# paris_wheel.net
KiCad netlist of a schematic drawn in EAGLE
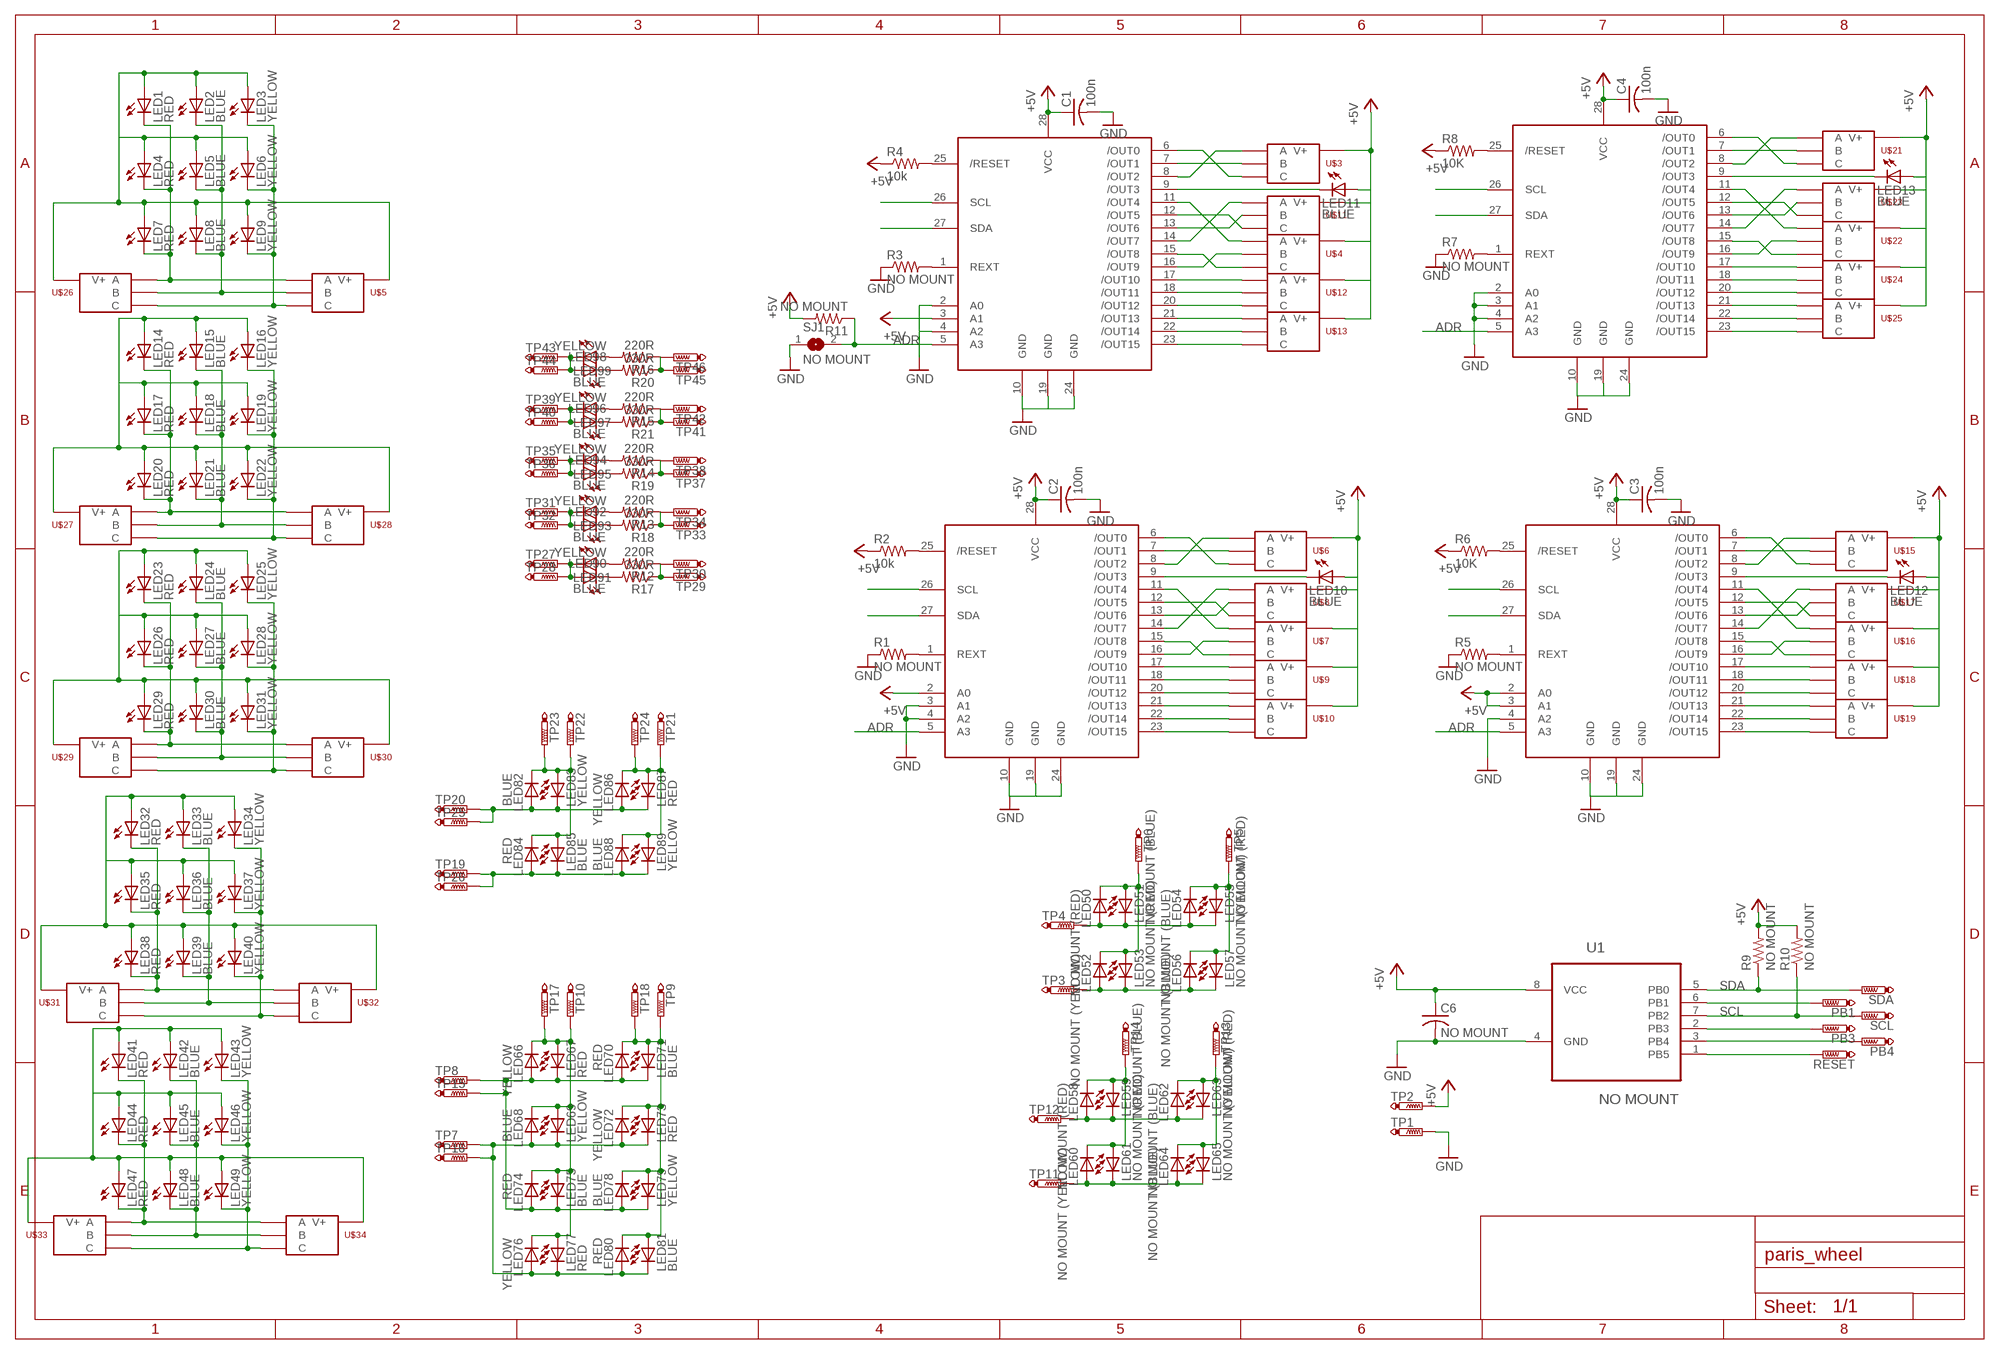
[diagram p0: schematic, sheet 1]

(export (version "E")
  (design (tool "Eeschema 10.0.6"))
  (components
    (comp (ref "C1")
      (value "100n")
      (footprint "eagle-import:C0603")
      (libsource (lib "eagle-import") (part "C-USC0603"))
    )
    (comp (ref "C2")
      (value "100n")
      (footprint "eagle-import:C0603")
      (libsource (lib "eagle-import") (part "C-USC0603"))
    )
    (comp (ref "C3")
      (value "100n")
      (footprint "eagle-import:C0603")
      (libsource (lib "eagle-import") (part "C-USC0603"))
    )
    (comp (ref "C4")
      (value "100n")
      (footprint "eagle-import:C0603")
      (libsource (lib "eagle-import") (part "C-USC0603"))
    )
    (comp (ref "C6")
      (value "NO MOUNT")
      (footprint "eagle-import:C0603")
      (libsource (lib "eagle-import") (part "C-USC0603"))
    )
    (comp (ref "LED1")
      (value "RED")
      (footprint "eagle-import:CHIP-LED0603")
      (libsource (lib "eagle-import") (part "LEDCHIP-LED0603"))
    )
    (comp (ref "LED2")
      (value "BLUE")
      (footprint "eagle-import:CHIP-LED0603")
      (libsource (lib "eagle-import") (part "LEDCHIP-LED0603"))
    )
    (comp (ref "LED3")
      (value "YELLOW")
      (footprint "eagle-import:CHIP-LED0603")
      (libsource (lib "eagle-import") (part "LEDCHIP-LED0603"))
    )
    (comp (ref "LED4")
      (value "RED")
      (footprint "eagle-import:CHIP-LED0603")
      (libsource (lib "eagle-import") (part "LEDCHIP-LED0603"))
    )
    (comp (ref "LED5")
      (value "BLUE")
      (footprint "eagle-import:CHIP-LED0603")
      (libsource (lib "eagle-import") (part "LEDCHIP-LED0603"))
    )
    (comp (ref "LED6")
      (value "YELLOW")
      (footprint "eagle-import:CHIP-LED0603")
      (libsource (lib "eagle-import") (part "LEDCHIP-LED0603"))
    )
    (comp (ref "LED7")
      (value "RED")
      (footprint "eagle-import:CHIP-LED0603")
      (libsource (lib "eagle-import") (part "LEDCHIP-LED0603"))
    )
    (comp (ref "LED8")
      (value "BLUE")
      (footprint "eagle-import:CHIP-LED0603")
      (libsource (lib "eagle-import") (part "LEDCHIP-LED0603"))
    )
    (comp (ref "LED9")
      (value "YELLOW")
      (footprint "eagle-import:CHIP-LED0603")
      (libsource (lib "eagle-import") (part "LEDCHIP-LED0603"))
    )
    (comp (ref "LED10")
      (value "BLUE")
      (footprint "eagle-import:CHIP-LED0603")
      (libsource (lib "eagle-import") (part "LEDCHIP-LED0603"))
    )
    (comp (ref "LED11")
      (value "BLUE")
      (footprint "eagle-import:CHIP-LED0603")
      (libsource (lib "eagle-import") (part "LEDCHIP-LED0603"))
    )
    (comp (ref "LED12")
      (value "BLUE")
      (footprint "eagle-import:CHIP-LED0603")
      (libsource (lib "eagle-import") (part "LEDCHIP-LED0603"))
    )
    (comp (ref "LED13")
      (value "BLUE")
      (footprint "eagle-import:CHIP-LED0603")
      (libsource (lib "eagle-import") (part "LEDCHIP-LED0603"))
    )
    (comp (ref "LED14")
      (value "RED")
      (footprint "eagle-import:CHIP-LED0603")
      (libsource (lib "eagle-import") (part "LEDCHIP-LED0603"))
    )
    (comp (ref "LED15")
      (value "BLUE")
      (footprint "eagle-import:CHIP-LED0603")
      (libsource (lib "eagle-import") (part "LEDCHIP-LED0603"))
    )
    (comp (ref "LED16")
      (value "YELLOW")
      (footprint "eagle-import:CHIP-LED0603")
      (libsource (lib "eagle-import") (part "LEDCHIP-LED0603"))
    )
    (comp (ref "LED17")
      (value "RED")
      (footprint "eagle-import:CHIP-LED0603")
      (libsource (lib "eagle-import") (part "LEDCHIP-LED0603"))
    )
    (comp (ref "LED18")
      (value "BLUE")
      (footprint "eagle-import:CHIP-LED0603")
      (libsource (lib "eagle-import") (part "LEDCHIP-LED0603"))
    )
    (comp (ref "LED19")
      (value "YELLOW")
      (footprint "eagle-import:CHIP-LED0603")
      (libsource (lib "eagle-import") (part "LEDCHIP-LED0603"))
    )
    (comp (ref "LED20")
      (value "RED")
      (footprint "eagle-import:CHIP-LED0603")
      (libsource (lib "eagle-import") (part "LEDCHIP-LED0603"))
    )
    (comp (ref "LED21")
      (value "BLUE")
      (footprint "eagle-import:CHIP-LED0603")
      (libsource (lib "eagle-import") (part "LEDCHIP-LED0603"))
    )
    (comp (ref "LED22")
      (value "YELLOW")
      (footprint "eagle-import:CHIP-LED0603")
      (libsource (lib "eagle-import") (part "LEDCHIP-LED0603"))
    )
    (comp (ref "LED23")
      (value "RED")
      (footprint "eagle-import:CHIP-LED0603")
      (libsource (lib "eagle-import") (part "LEDCHIP-LED0603"))
    )
    (comp (ref "LED24")
      (value "BLUE")
      (footprint "eagle-import:CHIP-LED0603")
      (libsource (lib "eagle-import") (part "LEDCHIP-LED0603"))
    )
    (comp (ref "LED25")
      (value "YELLOW")
      (footprint "eagle-import:CHIP-LED0603")
      (libsource (lib "eagle-import") (part "LEDCHIP-LED0603"))
    )
    (comp (ref "LED26")
      (value "RED")
      (footprint "eagle-import:CHIP-LED0603")
      (libsource (lib "eagle-import") (part "LEDCHIP-LED0603"))
    )
    (comp (ref "LED27")
      (value "BLUE")
      (footprint "eagle-import:CHIP-LED0603")
      (libsource (lib "eagle-import") (part "LEDCHIP-LED0603"))
    )
    (comp (ref "LED28")
      (value "YELLOW")
      (footprint "eagle-import:CHIP-LED0603")
      (libsource (lib "eagle-import") (part "LEDCHIP-LED0603"))
    )
    (comp (ref "LED29")
      (value "RED")
      (footprint "eagle-import:CHIP-LED0603")
      (libsource (lib "eagle-import") (part "LEDCHIP-LED0603"))
    )
    (comp (ref "LED30")
      (value "BLUE")
      (footprint "eagle-import:CHIP-LED0603")
      (libsource (lib "eagle-import") (part "LEDCHIP-LED0603"))
    )
    (comp (ref "LED31")
      (value "YELLOW")
      (footprint "eagle-import:CHIP-LED0603")
      (libsource (lib "eagle-import") (part "LEDCHIP-LED0603"))
    )
    (comp (ref "LED32")
      (value "RED")
      (footprint "eagle-import:CHIP-LED0603")
      (libsource (lib "eagle-import") (part "LEDCHIP-LED0603"))
    )
    (comp (ref "LED33")
      (value "BLUE")
      (footprint "eagle-import:CHIP-LED0603")
      (libsource (lib "eagle-import") (part "LEDCHIP-LED0603"))
    )
    (comp (ref "LED34")
      (value "YELLOW")
      (footprint "eagle-import:CHIP-LED0603")
      (libsource (lib "eagle-import") (part "LEDCHIP-LED0603"))
    )
    (comp (ref "LED35")
      (value "RED")
      (footprint "eagle-import:CHIP-LED0603")
      (libsource (lib "eagle-import") (part "LEDCHIP-LED0603"))
    )
    (comp (ref "LED36")
      (value "BLUE")
      (footprint "eagle-import:CHIP-LED0603")
      (libsource (lib "eagle-import") (part "LEDCHIP-LED0603"))
    )
    (comp (ref "LED37")
      (value "YELLOW")
      (footprint "eagle-import:CHIP-LED0603")
      (libsource (lib "eagle-import") (part "LEDCHIP-LED0603"))
    )
    (comp (ref "LED38")
      (value "RED")
      (footprint "eagle-import:CHIP-LED0603")
      (libsource (lib "eagle-import") (part "LEDCHIP-LED0603"))
    )
    (comp (ref "LED39")
      (value "BLUE")
      (footprint "eagle-import:CHIP-LED0603")
      (libsource (lib "eagle-import") (part "LEDCHIP-LED0603"))
    )
    (comp (ref "LED40")
      (value "YELLOW")
      (footprint "eagle-import:CHIP-LED0603")
      (libsource (lib "eagle-import") (part "LEDCHIP-LED0603"))
    )
    (comp (ref "LED41")
      (value "RED")
      (footprint "eagle-import:CHIP-LED0603")
      (libsource (lib "eagle-import") (part "LEDCHIP-LED0603"))
    )
    (comp (ref "LED42")
      (value "BLUE")
      (footprint "eagle-import:CHIP-LED0603")
      (libsource (lib "eagle-import") (part "LEDCHIP-LED0603"))
    )
    (comp (ref "LED43")
      (value "YELLOW")
      (footprint "eagle-import:CHIP-LED0603")
      (libsource (lib "eagle-import") (part "LEDCHIP-LED0603"))
    )
    (comp (ref "LED44")
      (value "RED")
      (footprint "eagle-import:CHIP-LED0603")
      (libsource (lib "eagle-import") (part "LEDCHIP-LED0603"))
    )
    (comp (ref "LED45")
      (value "BLUE")
      (footprint "eagle-import:CHIP-LED0603")
      (libsource (lib "eagle-import") (part "LEDCHIP-LED0603"))
    )
    (comp (ref "LED46")
      (value "YELLOW")
      (footprint "eagle-import:CHIP-LED0603")
      (libsource (lib "eagle-import") (part "LEDCHIP-LED0603"))
    )
    (comp (ref "LED47")
      (value "RED")
      (footprint "eagle-import:CHIP-LED0603")
      (libsource (lib "eagle-import") (part "LEDCHIP-LED0603"))
    )
    (comp (ref "LED48")
      (value "BLUE")
      (footprint "eagle-import:CHIP-LED0603")
      (libsource (lib "eagle-import") (part "LEDCHIP-LED0603"))
    )
    (comp (ref "LED49")
      (value "YELLOW")
      (footprint "eagle-import:CHIP-LED0603")
      (libsource (lib "eagle-import") (part "LEDCHIP-LED0603"))
    )
    (comp (ref "LED50")
      (value "NO MOUNT (RED)")
      (footprint "eagle-import:CHIP-LED0603")
      (libsource (lib "eagle-import") (part "LEDCHIP-LED0603"))
    )
    (comp (ref "LED51")
      (value "NO MOUNT (BLUE)")
      (footprint "eagle-import:CHIP-LED0603")
      (libsource (lib "eagle-import") (part "LEDCHIP-LED0603"))
    )
    (comp (ref "LED52")
      (value "NO MOUNT (YELLOW)")
      (footprint "eagle-import:CHIP-LED0603")
      (libsource (lib "eagle-import") (part "LEDCHIP-LED0603"))
    )
    (comp (ref "LED53")
      (value "NO MOUNT (RED)")
      (footprint "eagle-import:CHIP-LED0603")
      (libsource (lib "eagle-import") (part "LEDCHIP-LED0603"))
    )
    (comp (ref "LED54")
      (value "NO MOUNT (BLUE)")
      (footprint "eagle-import:CHIP-LED0603")
      (libsource (lib "eagle-import") (part "LEDCHIP-LED0603"))
    )
    (comp (ref "LED55")
      (value "NO MOUNT (RED)")
      (footprint "eagle-import:CHIP-LED0603")
      (libsource (lib "eagle-import") (part "LEDCHIP-LED0603"))
    )
    (comp (ref "LED56")
      (value "NO MOUNT (BLUE)")
      (footprint "eagle-import:CHIP-LED0603")
      (libsource (lib "eagle-import") (part "LEDCHIP-LED0603"))
    )
    (comp (ref "LED57")
      (value "NO MOUNT (YELLOW)")
      (footprint "eagle-import:CHIP-LED0603")
      (libsource (lib "eagle-import") (part "LEDCHIP-LED0603"))
    )
    (comp (ref "LED58")
      (value "NO MOUNT (RED)")
      (footprint "eagle-import:CHIP-LED0603")
      (libsource (lib "eagle-import") (part "LEDCHIP-LED0603"))
    )
    (comp (ref "LED59")
      (value "NO MOUNT (BLUE)")
      (footprint "eagle-import:CHIP-LED0603")
      (libsource (lib "eagle-import") (part "LEDCHIP-LED0603"))
    )
    (comp (ref "LED60")
      (value "NO MOUNT (YELLOW)")
      (footprint "eagle-import:CHIP-LED0603")
      (libsource (lib "eagle-import") (part "LEDCHIP-LED0603"))
    )
    (comp (ref "LED61")
      (value "NO MOUNT (RED)")
      (footprint "eagle-import:CHIP-LED0603")
      (libsource (lib "eagle-import") (part "LEDCHIP-LED0603"))
    )
    (comp (ref "LED62")
      (value "NO MOUNT (BLUE)")
      (footprint "eagle-import:CHIP-LED0603")
      (libsource (lib "eagle-import") (part "LEDCHIP-LED0603"))
    )
    (comp (ref "LED63")
      (value "NO MOUNT (RED)")
      (footprint "eagle-import:CHIP-LED0603")
      (libsource (lib "eagle-import") (part "LEDCHIP-LED0603"))
    )
    (comp (ref "LED64")
      (value "NO MOUNT (BLUE)")
      (footprint "eagle-import:CHIP-LED0603")
      (libsource (lib "eagle-import") (part "LEDCHIP-LED0603"))
    )
    (comp (ref "LED65")
      (value "NO MOUNT (YELLOW)")
      (footprint "eagle-import:CHIP-LED0603")
      (libsource (lib "eagle-import") (part "LEDCHIP-LED0603"))
    )
    (comp (ref "LED66")
      (value "YELLOW")
      (footprint "eagle-import:CHIP-LED0603")
      (libsource (lib "eagle-import") (part "LEDCHIP-LED0603"))
    )
    (comp (ref "LED67")
      (value "RED")
      (footprint "eagle-import:CHIP-LED0603")
      (libsource (lib "eagle-import") (part "LEDCHIP-LED0603"))
    )
    (comp (ref "LED68")
      (value "BLUE")
      (footprint "eagle-import:CHIP-LED0603")
      (libsource (lib "eagle-import") (part "LEDCHIP-LED0603"))
    )
    (comp (ref "LED69")
      (value "YELLOW")
      (footprint "eagle-import:CHIP-LED0603")
      (libsource (lib "eagle-import") (part "LEDCHIP-LED0603"))
    )
    (comp (ref "LED70")
      (value "RED")
      (footprint "eagle-import:CHIP-LED0603")
      (libsource (lib "eagle-import") (part "LEDCHIP-LED0603"))
    )
    (comp (ref "LED71")
      (value "BLUE")
      (footprint "eagle-import:CHIP-LED0603")
      (libsource (lib "eagle-import") (part "LEDCHIP-LED0603"))
    )
    (comp (ref "LED72")
      (value "YELLOW")
      (footprint "eagle-import:CHIP-LED0603")
      (libsource (lib "eagle-import") (part "LEDCHIP-LED0603"))
    )
    (comp (ref "LED73")
      (value "RED")
      (footprint "eagle-import:CHIP-LED0603")
      (libsource (lib "eagle-import") (part "LEDCHIP-LED0603"))
    )
    (comp (ref "LED74")
      (value "RED")
      (footprint "eagle-import:CHIP-LED0603")
      (libsource (lib "eagle-import") (part "LEDCHIP-LED0603"))
    )
    (comp (ref "LED75")
      (value "BLUE")
      (footprint "eagle-import:CHIP-LED0603")
      (libsource (lib "eagle-import") (part "LEDCHIP-LED0603"))
    )
    (comp (ref "LED76")
      (value "YELLOW")
      (footprint "eagle-import:CHIP-LED0603")
      (libsource (lib "eagle-import") (part "LEDCHIP-LED0603"))
    )
    (comp (ref "LED77")
      (value "RED")
      (footprint "eagle-import:CHIP-LED0603")
      (libsource (lib "eagle-import") (part "LEDCHIP-LED0603"))
    )
    (comp (ref "LED78")
      (value "BLUE")
      (footprint "eagle-import:CHIP-LED0603")
      (libsource (lib "eagle-import") (part "LEDCHIP-LED0603"))
    )
    (comp (ref "LED79")
      (value "YELLOW")
      (footprint "eagle-import:CHIP-LED0603")
      (libsource (lib "eagle-import") (part "LEDCHIP-LED0603"))
    )
    (comp (ref "LED80")
      (value "RED")
      (footprint "eagle-import:CHIP-LED0603")
      (libsource (lib "eagle-import") (part "LEDCHIP-LED0603"))
    )
    (comp (ref "LED81")
      (value "BLUE")
      (footprint "eagle-import:CHIP-LED0603")
      (libsource (lib "eagle-import") (part "LEDCHIP-LED0603"))
    )
    (comp (ref "LED82")
      (value "BLUE")
      (footprint "eagle-import:CHIP-LED0603")
      (libsource (lib "eagle-import") (part "LEDCHIP-LED0603"))
    )
    (comp (ref "LED83")
      (value "YELLOW")
      (footprint "eagle-import:CHIP-LED0603")
      (libsource (lib "eagle-import") (part "LEDCHIP-LED0603"))
    )
    (comp (ref "LED84")
      (value "RED")
      (footprint "eagle-import:CHIP-LED0603")
      (libsource (lib "eagle-import") (part "LEDCHIP-LED0603"))
    )
    (comp (ref "LED85")
      (value "BLUE")
      (footprint "eagle-import:CHIP-LED0603")
      (libsource (lib "eagle-import") (part "LEDCHIP-LED0603"))
    )
    (comp (ref "LED86")
      (value "YELLOW")
      (footprint "eagle-import:CHIP-LED0603")
      (libsource (lib "eagle-import") (part "LEDCHIP-LED0603"))
    )
    (comp (ref "LED87")
      (value "RED")
      (footprint "eagle-import:CHIP-LED0603")
      (libsource (lib "eagle-import") (part "LEDCHIP-LED0603"))
    )
    (comp (ref "LED88")
      (value "BLUE")
      (footprint "eagle-import:CHIP-LED0603")
      (libsource (lib "eagle-import") (part "LEDCHIP-LED0603"))
    )
    (comp (ref "LED89")
      (value "YELLOW")
      (footprint "eagle-import:CHIP-LED0603")
      (libsource (lib "eagle-import") (part "LEDCHIP-LED0603"))
    )
    (comp (ref "LED90")
      (value "YELLOW")
      (footprint "eagle-import:CHIP-LED0603")
      (libsource (lib "eagle-import") (part "LEDCHIP-LED0603"))
    )
    (comp (ref "LED91")
      (value "BLUE")
      (footprint "eagle-import:CHIP-LED0603")
      (libsource (lib "eagle-import") (part "LEDCHIP-LED0603"))
    )
    (comp (ref "LED92")
      (value "YELLOW")
      (footprint "eagle-import:CHIP-LED0603")
      (libsource (lib "eagle-import") (part "LEDCHIP-LED0603"))
    )
    (comp (ref "LED93")
      (value "BLUE")
      (footprint "eagle-import:CHIP-LED0603")
      (libsource (lib "eagle-import") (part "LEDCHIP-LED0603"))
    )
    (comp (ref "LED94")
      (value "YELLOW")
      (footprint "eagle-import:CHIP-LED0603")
      (libsource (lib "eagle-import") (part "LEDCHIP-LED0603"))
    )
    (comp (ref "LED95")
      (value "BLUE")
      (footprint "eagle-import:CHIP-LED0603")
      (libsource (lib "eagle-import") (part "LEDCHIP-LED0603"))
    )
    (comp (ref "LED96")
      (value "YELLOW")
      (footprint "eagle-import:CHIP-LED0603")
      (libsource (lib "eagle-import") (part "LEDCHIP-LED0603"))
    )
    (comp (ref "LED97")
      (value "BLUE")
      (footprint "eagle-import:CHIP-LED0603")
      (libsource (lib "eagle-import") (part "LEDCHIP-LED0603"))
    )
    (comp (ref "LED98")
      (value "YELLOW")
      (footprint "eagle-import:CHIP-LED0603")
      (libsource (lib "eagle-import") (part "LEDCHIP-LED0603"))
    )
    (comp (ref "LED99")
      (value "BLUE")
      (footprint "eagle-import:CHIP-LED0603")
      (libsource (lib "eagle-import") (part "LEDCHIP-LED0603"))
    )
    (comp (ref "PB1")
      (value "TESTPAD")
      (footprint "eagle-import:TP20SQ")
      (libsource (lib "eagle-import") (part "PTR1TP20SQ"))
    )
    (comp (ref "PB3")
      (value "TESTPAD")
      (footprint "eagle-import:TP20SQ")
      (libsource (lib "eagle-import") (part "PTR1TP20SQ"))
    )
    (comp (ref "PB4")
      (value "TESTPAD")
      (footprint "eagle-import:TP20SQ")
      (libsource (lib "eagle-import") (part "PTR1TP20SQ"))
    )
    (comp (ref "R1")
      (value "NO MOUNT")
      (footprint "eagle-import:R0603")
      (libsource (lib "eagle-import") (part "R-US_R0603"))
    )
    (comp (ref "R2")
      (value "10k")
      (footprint "eagle-import:R0603")
      (libsource (lib "eagle-import") (part "R-US_R0603"))
    )
    (comp (ref "R3")
      (value "NO MOUNT")
      (footprint "eagle-import:R0603")
      (libsource (lib "eagle-import") (part "R-US_R0603"))
    )
    (comp (ref "R4")
      (value "10k")
      (footprint "eagle-import:R0603")
      (libsource (lib "eagle-import") (part "R-US_R0603"))
    )
    (comp (ref "R5")
      (value "NO MOUNT")
      (footprint "eagle-import:R0603")
      (libsource (lib "eagle-import") (part "R-US_R0603"))
    )
    (comp (ref "R6")
      (value "10K")
      (footprint "eagle-import:R0603")
      (libsource (lib "eagle-import") (part "R-US_R0603"))
    )
    (comp (ref "R7")
      (value "NO MOUNT")
      (footprint "eagle-import:R0603")
      (libsource (lib "eagle-import") (part "R-US_R0603"))
    )
    (comp (ref "R8")
      (value "10K")
      (footprint "eagle-import:R0603")
      (libsource (lib "eagle-import") (part "R-US_R0603"))
    )
    (comp (ref "R9")
      (value "NO MOUNT")
      (footprint "eagle-import:R0603")
      (libsource (lib "eagle-import") (part "R-US_R0603"))
    )
    (comp (ref "R10")
      (value "NO MOUNT")
      (footprint "eagle-import:R0603")
      (libsource (lib "eagle-import") (part "R-US_R0603"))
    )
    (comp (ref "R11")
      (value "NO MOUNT")
      (footprint "eagle-import:R0603")
      (libsource (lib "eagle-import") (part "R-US_R0603"))
    )
    (comp (ref "R12")
      (value "220R")
      (footprint "eagle-import:R0603")
      (libsource (lib "eagle-import") (part "R-US_R0603"))
    )
    (comp (ref "R13")
      (value "220R")
      (footprint "eagle-import:R0603")
      (libsource (lib "eagle-import") (part "R-US_R0603"))
    )
    (comp (ref "R14")
      (value "220R")
      (footprint "eagle-import:R0603")
      (libsource (lib "eagle-import") (part "R-US_R0603"))
    )
    (comp (ref "R15")
      (value "220R")
      (footprint "eagle-import:R0603")
      (libsource (lib "eagle-import") (part "R-US_R0603"))
    )
    (comp (ref "R16")
      (value "220R")
      (footprint "eagle-import:R0603")
      (libsource (lib "eagle-import") (part "R-US_R0603"))
    )
    (comp (ref "R17")
      (value "330R")
      (footprint "eagle-import:R0603")
      (libsource (lib "eagle-import") (part "R-US_R0603"))
    )
    (comp (ref "R18")
      (value "330R")
      (footprint "eagle-import:R0603")
      (libsource (lib "eagle-import") (part "R-US_R0603"))
    )
    (comp (ref "R19")
      (value "330R")
      (footprint "eagle-import:R0603")
      (libsource (lib "eagle-import") (part "R-US_R0603"))
    )
    (comp (ref "R20")
      (value "330R")
      (footprint "eagle-import:R0603")
      (libsource (lib "eagle-import") (part "R-US_R0603"))
    )
    (comp (ref "R21")
      (value "330R")
      (footprint "eagle-import:R0603")
      (libsource (lib "eagle-import") (part "R-US_R0603"))
    )
    (comp (ref "RESET")
      (value "TESTPAD")
      (footprint "eagle-import:TP20SQ")
      (libsource (lib "eagle-import") (part "PTR1TP20SQ"))
    )
    (comp (ref "SCL")
      (value "TESTPAD")
      (footprint "eagle-import:TP20SQ")
      (libsource (lib "eagle-import") (part "PTR1TP20SQ"))
    )
    (comp (ref "SDA")
      (value "TESTPAD")
      (footprint "eagle-import:TP20SQ")
      (libsource (lib "eagle-import") (part "PTR1TP20SQ"))
    )
    (comp (ref "SJ1")
      (value "NO MOUNT")
      (footprint "eagle-import:SJ")
      (libsource (lib "eagle-import") (part "SJ"))
    )
    (comp (ref "TP1")
      (value "TESTPAD")
      (footprint "eagle-import:TP20SQ")
      (libsource (lib "eagle-import") (part "PTR1TP20SQ"))
    )
    (comp (ref "TP2")
      (value "TESTPAD")
      (footprint "eagle-import:TP20SQ")
      (libsource (lib "eagle-import") (part "PTR1TP20SQ"))
    )
    (comp (ref "TP3")
      (value "TESTPAD")
      (footprint "eagle-import:TP15SQ")
      (libsource (lib "eagle-import") (part "PTR1TP15SQ"))
    )
    (comp (ref "TP4")
      (value "TESTPAD")
      (footprint "eagle-import:TP15SQ")
      (libsource (lib "eagle-import") (part "PTR1TP15SQ"))
    )
    (comp (ref "TP5")
      (value "TESTPAD")
      (footprint "eagle-import:TP15SQ")
      (libsource (lib "eagle-import") (part "PTR1TP15SQ"))
    )
    (comp (ref "TP6")
      (value "TESTPAD")
      (footprint "eagle-import:TP15SQ")
      (libsource (lib "eagle-import") (part "PTR1TP15SQ"))
    )
    (comp (ref "TP7")
      (value "TESTPAD")
      (footprint "eagle-import:TP15SQ")
      (libsource (lib "eagle-import") (part "PTR1TP15SQ"))
    )
    (comp (ref "TP8")
      (value "TESTPAD")
      (footprint "eagle-import:TP15SQ")
      (libsource (lib "eagle-import") (part "PTR1TP15SQ"))
    )
    (comp (ref "TP9")
      (value "TESTPAD")
      (footprint "eagle-import:TP15SQ")
      (libsource (lib "eagle-import") (part "PTR1TP15SQ"))
    )
    (comp (ref "TP10")
      (value "TESTPAD")
      (footprint "eagle-import:TP15SQ")
      (libsource (lib "eagle-import") (part "PTR1TP15SQ"))
    )
    (comp (ref "TP11")
      (value "TESTPAD")
      (footprint "eagle-import:TP15SQ")
      (libsource (lib "eagle-import") (part "PTR1TP15SQ"))
    )
    (comp (ref "TP12")
      (value "TESTPAD")
      (footprint "eagle-import:TP15SQ")
      (libsource (lib "eagle-import") (part "PTR1TP15SQ"))
    )
    (comp (ref "TP13")
      (value "TESTPAD")
      (footprint "eagle-import:TP15SQ")
      (libsource (lib "eagle-import") (part "PTR1TP15SQ"))
    )
    (comp (ref "TP14")
      (value "TESTPAD")
      (footprint "eagle-import:TP15SQ")
      (libsource (lib "eagle-import") (part "PTR1TP15SQ"))
    )
    (comp (ref "TP15")
      (value "TESTPAD")
      (footprint "eagle-import:TP15SQ")
      (libsource (lib "eagle-import") (part "PTR1TP15SQ"))
    )
    (comp (ref "TP16")
      (value "TESTPAD")
      (footprint "eagle-import:TP15SQ")
      (libsource (lib "eagle-import") (part "PTR1TP15SQ"))
    )
    (comp (ref "TP17")
      (value "TESTPAD")
      (footprint "eagle-import:TP15SQ")
      (libsource (lib "eagle-import") (part "PTR1TP15SQ"))
    )
    (comp (ref "TP18")
      (value "TESTPAD")
      (footprint "eagle-import:TP15SQ")
      (libsource (lib "eagle-import") (part "PTR1TP15SQ"))
    )
    (comp (ref "TP19")
      (value "TESTPAD")
      (footprint "eagle-import:TP15SQ")
      (libsource (lib "eagle-import") (part "PTR1TP15SQ"))
    )
    (comp (ref "TP20")
      (value "TESTPAD")
      (footprint "eagle-import:TP15SQ")
      (libsource (lib "eagle-import") (part "PTR1TP15SQ"))
    )
    (comp (ref "TP21")
      (value "TESTPAD")
      (footprint "eagle-import:TP15SQ")
      (libsource (lib "eagle-import") (part "PTR1TP15SQ"))
    )
    (comp (ref "TP22")
      (value "TESTPAD")
      (footprint "eagle-import:TP15SQ")
      (libsource (lib "eagle-import") (part "PTR1TP15SQ"))
    )
    (comp (ref "TP23")
      (value "TESTPAD")
      (footprint "eagle-import:TP15SQ")
      (libsource (lib "eagle-import") (part "PTR1TP15SQ"))
    )
    (comp (ref "TP24")
      (value "TESTPAD")
      (footprint "eagle-import:TP15SQ")
      (libsource (lib "eagle-import") (part "PTR1TP15SQ"))
    )
    (comp (ref "TP25")
      (value "TESTPAD")
      (footprint "eagle-import:TP15SQ")
      (libsource (lib "eagle-import") (part "PTR1TP15SQ"))
    )
    (comp (ref "TP26")
      (value "TESTPAD")
      (footprint "eagle-import:TP15SQ")
      (libsource (lib "eagle-import") (part "PTR1TP15SQ"))
    )
    (comp (ref "TP27")
      (value "TESTPAD")
      (footprint "eagle-import:TP15SQ")
      (libsource (lib "eagle-import") (part "PTR1TP15SQ"))
    )
    (comp (ref "TP28")
      (value "TESTPAD")
      (footprint "eagle-import:TP15SQ")
      (libsource (lib "eagle-import") (part "PTR1TP15SQ"))
    )
    (comp (ref "TP29")
      (value "TESTPAD")
      (footprint "eagle-import:TP15SQ")
      (libsource (lib "eagle-import") (part "PTR1TP15SQ"))
    )
    (comp (ref "TP30")
      (value "TESTPAD")
      (footprint "eagle-import:TP15SQ")
      (libsource (lib "eagle-import") (part "PTR1TP15SQ"))
    )
    (comp (ref "TP31")
      (value "TESTPAD")
      (footprint "eagle-import:TP15SQ")
      (libsource (lib "eagle-import") (part "PTR1TP15SQ"))
    )
    (comp (ref "TP32")
      (value "TESTPAD")
      (footprint "eagle-import:TP15SQ")
      (libsource (lib "eagle-import") (part "PTR1TP15SQ"))
    )
    (comp (ref "TP33")
      (value "TESTPAD")
      (footprint "eagle-import:TP15SQ")
      (libsource (lib "eagle-import") (part "PTR1TP15SQ"))
    )
    (comp (ref "TP34")
      (value "TESTPAD")
      (footprint "eagle-import:TP15SQ")
      (libsource (lib "eagle-import") (part "PTR1TP15SQ"))
    )
    (comp (ref "TP35")
      (value "TESTPAD")
      (footprint "eagle-import:TP15SQ")
      (libsource (lib "eagle-import") (part "PTR1TP15SQ"))
    )
    (comp (ref "TP36")
      (value "TESTPAD")
      (footprint "eagle-import:TP15SQ")
      (libsource (lib "eagle-import") (part "PTR1TP15SQ"))
    )
    (comp (ref "TP37")
      (value "TESTPAD")
      (footprint "eagle-import:TP15SQ")
      (libsource (lib "eagle-import") (part "PTR1TP15SQ"))
    )
    (comp (ref "TP38")
      (value "TESTPAD")
      (footprint "eagle-import:TP15SQ")
      (libsource (lib "eagle-import") (part "PTR1TP15SQ"))
    )
    (comp (ref "TP39")
      (value "TESTPAD")
      (footprint "eagle-import:TP15SQ")
      (libsource (lib "eagle-import") (part "PTR1TP15SQ"))
    )
    (comp (ref "TP40")
      (value "TESTPAD")
      (footprint "eagle-import:TP15SQ")
      (libsource (lib "eagle-import") (part "PTR1TP15SQ"))
    )
    (comp (ref "TP41")
      (value "TESTPAD")
      (footprint "eagle-import:TP15SQ")
      (libsource (lib "eagle-import") (part "PTR1TP15SQ"))
    )
    (comp (ref "TP42")
      (value "TESTPAD")
      (footprint "eagle-import:TP15SQ")
      (libsource (lib "eagle-import") (part "PTR1TP15SQ"))
    )
    (comp (ref "TP43")
      (value "TESTPAD")
      (footprint "eagle-import:TP15SQ")
      (libsource (lib "eagle-import") (part "PTR1TP15SQ"))
    )
    (comp (ref "TP44")
      (value "TESTPAD")
      (footprint "eagle-import:TP15SQ")
      (libsource (lib "eagle-import") (part "PTR1TP15SQ"))
    )
    (comp (ref "TP45")
      (value "TESTPAD")
      (footprint "eagle-import:TP15SQ")
      (libsource (lib "eagle-import") (part "PTR1TP15SQ"))
    )
    (comp (ref "TP46")
      (value "TESTPAD")
      (footprint "eagle-import:TP15SQ")
      (libsource (lib "eagle-import") (part "PTR1TP15SQ"))
    )
    (comp (ref "U$1")
      (value "TLC59116IPWR")
      (footprint "eagle-import:TSSOP28")
      (libsource (lib "eagle-import") (part "TLC59116"))
    )
    (comp (ref "U$2")
      (value "TLC59116IPWR")
      (footprint "eagle-import:TSSOP28")
      (libsource (lib "eagle-import") (part "TLC59116"))
    )
    (comp (ref "U$3")
      (value "NO MOUNT")
      (footprint "eagle-import:MINI-PCB-CONNECTOR")
      (libsource (lib "eagle-import") (part "MINI-PCB-CONNECTOR-DRIVE-SIDE"))
    )
    (comp (ref "U$4")
      (value "NO MOUNT")
      (footprint "eagle-import:MINI-PCB-CONNECTOR")
      (libsource (lib "eagle-import") (part "MINI-PCB-CONNECTOR-DRIVE-SIDE"))
    )
    (comp (ref "U$5")
      (value "NO MOUNT")
      (footprint "eagle-import:MINI-PCB-CONNECTOR")
      (libsource (lib "eagle-import") (part "MINI-PCB-CONNECTOR-DRIVE-SIDE"))
    )
    (comp (ref "U$6")
      (value "NO MOUNT")
      (footprint "eagle-import:MINI-PCB-CONNECTOR")
      (libsource (lib "eagle-import") (part "MINI-PCB-CONNECTOR-DRIVE-SIDE"))
    )
    (comp (ref "U$7")
      (value "NO MOUNT")
      (footprint "eagle-import:MINI-PCB-CONNECTOR")
      (libsource (lib "eagle-import") (part "MINI-PCB-CONNECTOR-DRIVE-SIDE"))
    )
    (comp (ref "U$8")
      (value "NO MOUNT")
      (footprint "eagle-import:MINI-PCB-CONNECTOR")
      (libsource (lib "eagle-import") (part "MINI-PCB-CONNECTOR-DRIVE-SIDE"))
    )
    (comp (ref "U$9")
      (value "NO MOUNT")
      (footprint "eagle-import:MINI-PCB-CONNECTOR")
      (libsource (lib "eagle-import") (part "MINI-PCB-CONNECTOR-DRIVE-SIDE"))
    )
    (comp (ref "U$10")
      (value "NO MOUNT")
      (footprint "eagle-import:MINI-PCB-CONNECTOR")
      (libsource (lib "eagle-import") (part "MINI-PCB-CONNECTOR-DRIVE-SIDE"))
    )
    (comp (ref "U$11")
      (value "NO MOUNT")
      (footprint "eagle-import:MINI-PCB-CONNECTOR")
      (libsource (lib "eagle-import") (part "MINI-PCB-CONNECTOR-DRIVE-SIDE"))
    )
    (comp (ref "U$12")
      (value "NO MOUNT")
      (footprint "eagle-import:MINI-PCB-CONNECTOR")
      (libsource (lib "eagle-import") (part "MINI-PCB-CONNECTOR-DRIVE-SIDE"))
    )
    (comp (ref "U$13")
      (value "NO MOUNT")
      (footprint "eagle-import:MINI-PCB-CONNECTOR")
      (libsource (lib "eagle-import") (part "MINI-PCB-CONNECTOR-DRIVE-SIDE"))
    )
    (comp (ref "U$14")
      (value "TLC59116IPWR")
      (footprint "eagle-import:TSSOP28")
      (libsource (lib "eagle-import") (part "TLC59116"))
    )
    (comp (ref "U$15")
      (value "NO MOUNT")
      (footprint "eagle-import:MINI-PCB-CONNECTOR")
      (libsource (lib "eagle-import") (part "MINI-PCB-CONNECTOR-DRIVE-SIDE"))
    )
    (comp (ref "U$16")
      (value "NO MOUNT")
      (footprint "eagle-import:MINI-PCB-CONNECTOR")
      (libsource (lib "eagle-import") (part "MINI-PCB-CONNECTOR-DRIVE-SIDE"))
    )
    (comp (ref "U$17")
      (value "NO MOUNT")
      (footprint "eagle-import:MINI-PCB-CONNECTOR")
      (libsource (lib "eagle-import") (part "MINI-PCB-CONNECTOR-DRIVE-SIDE"))
    )
    (comp (ref "U$18")
      (value "NO MOUNT")
      (footprint "eagle-import:MINI-PCB-CONNECTOR")
      (libsource (lib "eagle-import") (part "MINI-PCB-CONNECTOR-DRIVE-SIDE"))
    )
    (comp (ref "U$19")
      (value "NO MOUNT")
      (footprint "eagle-import:MINI-PCB-CONNECTOR")
      (libsource (lib "eagle-import") (part "MINI-PCB-CONNECTOR-DRIVE-SIDE"))
    )
    (comp (ref "U$20")
      (value "TLC59116IPWR")
      (footprint "eagle-import:TSSOP28")
      (libsource (lib "eagle-import") (part "TLC59116"))
    )
    (comp (ref "U$21")
      (value "NO MOUNT")
      (footprint "eagle-import:MINI-PCB-CONNECTOR")
      (libsource (lib "eagle-import") (part "MINI-PCB-CONNECTOR-DRIVE-SIDE"))
    )
    (comp (ref "U$22")
      (value "NO MOUNT")
      (footprint "eagle-import:MINI-PCB-CONNECTOR")
      (libsource (lib "eagle-import") (part "MINI-PCB-CONNECTOR-DRIVE-SIDE"))
    )
    (comp (ref "U$23")
      (value "NO MOUNT")
      (footprint "eagle-import:MINI-PCB-CONNECTOR")
      (libsource (lib "eagle-import") (part "MINI-PCB-CONNECTOR-DRIVE-SIDE"))
    )
    (comp (ref "U$24")
      (value "NO MOUNT")
      (footprint "eagle-import:MINI-PCB-CONNECTOR")
      (libsource (lib "eagle-import") (part "MINI-PCB-CONNECTOR-DRIVE-SIDE"))
    )
    (comp (ref "U$25")
      (value "NO MOUNT")
      (footprint "eagle-import:MINI-PCB-CONNECTOR")
      (libsource (lib "eagle-import") (part "MINI-PCB-CONNECTOR-DRIVE-SIDE"))
    )
    (comp (ref "U$26")
      (value "NO MOUNT")
      (footprint "eagle-import:MINI-PCB-CONNECTOR")
      (libsource (lib "eagle-import") (part "MINI-PCB-CONNECTOR-LED-SIDE"))
    )
    (comp (ref "U$27")
      (value "NO MOUNT")
      (footprint "eagle-import:MINI-PCB-CONNECTOR")
      (libsource (lib "eagle-import") (part "MINI-PCB-CONNECTOR-LED-SIDE"))
    )
    (comp (ref "U$28")
      (value "NO MOUNT")
      (footprint "eagle-import:MINI-PCB-CONNECTOR")
      (libsource (lib "eagle-import") (part "MINI-PCB-CONNECTOR-DRIVE-SIDE"))
    )
    (comp (ref "U$29")
      (value "NO MOUNT")
      (footprint "eagle-import:MINI-PCB-CONNECTOR")
      (libsource (lib "eagle-import") (part "MINI-PCB-CONNECTOR-LED-SIDE"))
    )
    (comp (ref "U$30")
      (value "NO MOUNT")
      (footprint "eagle-import:MINI-PCB-CONNECTOR")
      (libsource (lib "eagle-import") (part "MINI-PCB-CONNECTOR-DRIVE-SIDE"))
    )
    (comp (ref "U$31")
      (value "NO MOUNT")
      (footprint "eagle-import:MINI-PCB-CONNECTOR")
      (libsource (lib "eagle-import") (part "MINI-PCB-CONNECTOR-LED-SIDE"))
    )
    (comp (ref "U$32")
      (value "NO MOUNT")
      (footprint "eagle-import:MINI-PCB-CONNECTOR")
      (libsource (lib "eagle-import") (part "MINI-PCB-CONNECTOR-DRIVE-SIDE"))
    )
    (comp (ref "U$33")
      (value "NO MOUNT")
      (footprint "eagle-import:MINI-PCB-CONNECTOR")
      (libsource (lib "eagle-import") (part "MINI-PCB-CONNECTOR-LED-SIDE"))
    )
    (comp (ref "U$34")
      (value "NO MOUNT")
      (footprint "eagle-import:MINI-PCB-CONNECTOR")
      (libsource (lib "eagle-import") (part "MINI-PCB-CONNECTOR-DRIVE-SIDE"))
    )
    (comp (ref "U1")
      (value "NO MOUNT")
      (footprint "eagle-import:SOIC127P798X216-8N")
      (fields (field (name "MPN") "ATTINY85-20SU"))
      (libsource (lib "eagle-import") (part "ATTINY85-20SU"))
    )
  )
  (nets
    (net (code "1") (name "+5V") (class "Default")
      (node (ref "C1") (pin "1") (pinfunction "1_1") (pintype "passive"))
      (node (ref "C2") (pin "1") (pinfunction "1_1") (pintype "passive"))
      (node (ref "C3") (pin "1") (pinfunction "1_1") (pintype "passive"))
      (node (ref "C4") (pin "1") (pinfunction "1_1") (pintype "passive"))
      (node (ref "C6") (pin "1") (pinfunction "1_1") (pintype "passive"))
      (node (ref "LED10") (pin "A") (pinfunction "A_A") (pintype "passive"))
      (node (ref "LED11") (pin "A") (pinfunction "A_A") (pintype "passive"))
      (node (ref "LED12") (pin "A") (pinfunction "A_A") (pintype "passive"))
      (node (ref "LED13") (pin "A") (pinfunction "A_A") (pintype "passive"))
      (node (ref "R10") (pin "2") (pinfunction "2_2") (pintype "passive"))
      (node (ref "R11") (pin "2") (pinfunction "2_2") (pintype "passive"))
      (node (ref "R2") (pin "1") (pinfunction "1_1") (pintype "passive"))
      (node (ref "R4") (pin "1") (pinfunction "1_1") (pintype "passive"))
      (node (ref "R6") (pin "1") (pinfunction "1_1") (pintype "passive"))
      (node (ref "R8") (pin "1") (pinfunction "1_1") (pintype "passive"))
      (node (ref "R9") (pin "2") (pinfunction "2_2") (pintype "passive"))
      (node (ref "TP2") (pin "TP") (pinfunction "TP_TP") (pintype "input"))
      (node (ref "U$1") (pin "2") (pinfunction "A0_2") (pintype "bidirectional"))
      (node (ref "U$1") (pin "28") (pinfunction "VCC_28") (pintype "bidirectional"))
      (node (ref "U$10") (pin "A") (pinfunction "V+_A") (pintype "bidirectional"))
      (node (ref "U$11") (pin "A") (pinfunction "V+_A") (pintype "bidirectional"))
      (node (ref "U$12") (pin "A") (pinfunction "V+_A") (pintype "bidirectional"))
      (node (ref "U$13") (pin "A") (pinfunction "V+_A") (pintype "bidirectional"))
      (node (ref "U$14") (pin "2") (pinfunction "A0_2") (pintype "bidirectional"))
      (node (ref "U$14") (pin "28") (pinfunction "VCC_28") (pintype "bidirectional"))
      (node (ref "U$14") (pin "3") (pinfunction "A1_3") (pintype "bidirectional"))
      (node (ref "U$15") (pin "A") (pinfunction "V+_A") (pintype "bidirectional"))
      (node (ref "U$16") (pin "A") (pinfunction "V+_A") (pintype "bidirectional"))
      (node (ref "U$17") (pin "A") (pinfunction "V+_A") (pintype "bidirectional"))
      (node (ref "U$18") (pin "A") (pinfunction "V+_A") (pintype "bidirectional"))
      (node (ref "U$19") (pin "A") (pinfunction "V+_A") (pintype "bidirectional"))
      (node (ref "U$2") (pin "28") (pinfunction "VCC_28") (pintype "bidirectional"))
      (node (ref "U$2") (pin "3") (pinfunction "A1_3") (pintype "bidirectional"))
      (node (ref "U$20") (pin "28") (pinfunction "VCC_28") (pintype "bidirectional"))
      (node (ref "U$21") (pin "A") (pinfunction "V+_A") (pintype "bidirectional"))
      (node (ref "U$22") (pin "A") (pinfunction "V+_A") (pintype "bidirectional"))
      (node (ref "U$23") (pin "A") (pinfunction "V+_A") (pintype "bidirectional"))
      (node (ref "U$24") (pin "A") (pinfunction "V+_A") (pintype "bidirectional"))
      (node (ref "U$25") (pin "A") (pinfunction "V+_A") (pintype "bidirectional"))
      (node (ref "U$3") (pin "A") (pinfunction "V+_A") (pintype "bidirectional"))
      (node (ref "U$4") (pin "A") (pinfunction "V+_A") (pintype "bidirectional"))
      (node (ref "U$6") (pin "A") (pinfunction "V+_A") (pintype "bidirectional"))
      (node (ref "U$7") (pin "A") (pinfunction "V+_A") (pintype "bidirectional"))
      (node (ref "U$8") (pin "A") (pinfunction "V+_A") (pintype "bidirectional"))
      (node (ref "U$9") (pin "A") (pinfunction "V+_A") (pintype "bidirectional"))
      (node (ref "U1") (pin "8") (pinfunction "VCC_8") (pintype "power_in"))
    )
    (net (code "2") (name "/ADR") (class "Default")
      (node (ref "R11") (pin "1") (pinfunction "1_1") (pintype "passive"))
      (node (ref "SJ1") (pin "2") (pinfunction "2_2") (pintype "passive"))
      (node (ref "U$1") (pin "5") (pinfunction "A3_5") (pintype "bidirectional"))
      (node (ref "U$14") (pin "5") (pinfunction "A3_5") (pintype "bidirectional"))
      (node (ref "U$2") (pin "5") (pinfunction "A3_5") (pintype "bidirectional"))
      (node (ref "U$20") (pin "5") (pinfunction "A3_5") (pintype "bidirectional"))
    )
    (net (code "3") (name "/SCL") (class "Default")
      (node (ref "R10") (pin "1") (pinfunction "1_1") (pintype "passive"))
      (node (ref "SCL") (pin "TP") (pinfunction "TP_TP") (pintype "input"))
      (node (ref "U$1") (pin "26") (pinfunction "SCL_26") (pintype "bidirectional"))
      (node (ref "U$14") (pin "26") (pinfunction "SCL_26") (pintype "bidirectional"))
      (node (ref "U$2") (pin "26") (pinfunction "SCL_26") (pintype "bidirectional"))
      (node (ref "U$20") (pin "26") (pinfunction "SCL_26") (pintype "bidirectional"))
      (node (ref "U1") (pin "7") (pinfunction "PB2_7") (pintype "bidirectional"))
    )
    (net (code "4") (name "/SDA") (class "Default")
      (node (ref "R9") (pin "1") (pinfunction "1_1") (pintype "passive"))
      (node (ref "SDA") (pin "TP") (pinfunction "TP_TP") (pintype "input"))
      (node (ref "U$1") (pin "27") (pinfunction "SDA_27") (pintype "bidirectional"))
      (node (ref "U$14") (pin "27") (pinfunction "SDA_27") (pintype "bidirectional"))
      (node (ref "U$2") (pin "27") (pinfunction "SDA_27") (pintype "bidirectional"))
      (node (ref "U$20") (pin "27") (pinfunction "SDA_27") (pintype "bidirectional"))
      (node (ref "U1") (pin "5") (pinfunction "PB0_5") (pintype "bidirectional"))
    )
    (net (code "5") (name "GND") (class "Default")
      (node (ref "C1") (pin "2") (pinfunction "2_2") (pintype "passive"))
      (node (ref "C2") (pin "2") (pinfunction "2_2") (pintype "passive"))
      (node (ref "C3") (pin "2") (pinfunction "2_2") (pintype "passive"))
      (node (ref "C4") (pin "2") (pinfunction "2_2") (pintype "passive"))
      (node (ref "C6") (pin "2") (pinfunction "2_2") (pintype "passive"))
      (node (ref "R1") (pin "1") (pinfunction "1_1") (pintype "passive"))
      (node (ref "R3") (pin "1") (pinfunction "1_1") (pintype "passive"))
      (node (ref "R5") (pin "1") (pinfunction "1_1") (pintype "passive"))
      (node (ref "R7") (pin "1") (pinfunction "1_1") (pintype "passive"))
      (node (ref "SJ1") (pin "1") (pinfunction "1_1") (pintype "passive"))
      (node (ref "TP1") (pin "TP") (pinfunction "TP_TP") (pintype "input"))
      (node (ref "U$1") (pin "10") (pinfunction "GND_10") (pintype "bidirectional"))
      (node (ref "U$1") (pin "19") (pinfunction "GND_19") (pintype "bidirectional"))
      (node (ref "U$1") (pin "24") (pinfunction "GND_24") (pintype "bidirectional"))
      (node (ref "U$1") (pin "3") (pinfunction "A1_3") (pintype "bidirectional"))
      (node (ref "U$1") (pin "4") (pinfunction "A2_4") (pintype "bidirectional"))
      (node (ref "U$14") (pin "10") (pinfunction "GND_10") (pintype "bidirectional"))
      (node (ref "U$14") (pin "19") (pinfunction "GND_19") (pintype "bidirectional"))
      (node (ref "U$14") (pin "24") (pinfunction "GND_24") (pintype "bidirectional"))
      (node (ref "U$14") (pin "4") (pinfunction "A2_4") (pintype "bidirectional"))
      (node (ref "U$2") (pin "10") (pinfunction "GND_10") (pintype "bidirectional"))
      (node (ref "U$2") (pin "19") (pinfunction "GND_19") (pintype "bidirectional"))
      (node (ref "U$2") (pin "2") (pinfunction "A0_2") (pintype "bidirectional"))
      (node (ref "U$2") (pin "24") (pinfunction "GND_24") (pintype "bidirectional"))
      (node (ref "U$2") (pin "4") (pinfunction "A2_4") (pintype "bidirectional"))
      (node (ref "U$20") (pin "10") (pinfunction "GND_10") (pintype "bidirectional"))
      (node (ref "U$20") (pin "19") (pinfunction "GND_19") (pintype "bidirectional"))
      (node (ref "U$20") (pin "2") (pinfunction "A0_2") (pintype "bidirectional"))
      (node (ref "U$20") (pin "24") (pinfunction "GND_24") (pintype "bidirectional"))
      (node (ref "U$20") (pin "3") (pinfunction "A1_3") (pintype "bidirectional"))
      (node (ref "U$20") (pin "4") (pinfunction "A2_4") (pintype "bidirectional"))
      (node (ref "U1") (pin "4") (pinfunction "GND_4") (pintype "passive"))
    )
    (net (code "6") (name "Net-(LED50-PadA)") (class "Default")
      (node (ref "LED50") (pin "A") (pinfunction "A_A") (pintype "passive"))
      (node (ref "LED51") (pin "C") (pinfunction "C_C") (pintype "passive"))
      (node (ref "LED54") (pin "A") (pinfunction "A_A") (pintype "passive"))
      (node (ref "LED55") (pin "C") (pinfunction "C_C") (pintype "passive"))
      (node (ref "TP4") (pin "TP") (pinfunction "TP_TP") (pintype "input"))
    )
    (net (code "7") (name "Net-(LED50-PadC)") (class "Default")
      (node (ref "LED50") (pin "C") (pinfunction "C_C") (pintype "passive"))
      (node (ref "LED51") (pin "A") (pinfunction "A_A") (pintype "passive"))
      (node (ref "LED52") (pin "C") (pinfunction "C_C") (pintype "passive"))
      (node (ref "LED53") (pin "A") (pinfunction "A_A") (pintype "passive"))
      (node (ref "TP6") (pin "TP") (pinfunction "TP_TP") (pintype "input"))
    )
    (net (code "8") (name "Net-(LED52-PadA)") (class "Default")
      (node (ref "LED52") (pin "A") (pinfunction "A_A") (pintype "passive"))
      (node (ref "LED53") (pin "C") (pinfunction "C_C") (pintype "passive"))
      (node (ref "LED56") (pin "A") (pinfunction "A_A") (pintype "passive"))
      (node (ref "LED57") (pin "C") (pinfunction "C_C") (pintype "passive"))
      (node (ref "TP3") (pin "TP") (pinfunction "TP_TP") (pintype "input"))
    )
    (net (code "9") (name "Net-(LED54-PadC)") (class "Default")
      (node (ref "LED54") (pin "C") (pinfunction "C_C") (pintype "passive"))
      (node (ref "LED55") (pin "A") (pinfunction "A_A") (pintype "passive"))
      (node (ref "LED56") (pin "C") (pinfunction "C_C") (pintype "passive"))
      (node (ref "LED57") (pin "A") (pinfunction "A_A") (pintype "passive"))
      (node (ref "TP5") (pin "TP") (pinfunction "TP_TP") (pintype "input"))
    )
    (net (code "10") (name "Net-(LED58-PadA)") (class "Default")
      (node (ref "LED58") (pin "A") (pinfunction "A_A") (pintype "passive"))
      (node (ref "LED59") (pin "C") (pinfunction "C_C") (pintype "passive"))
      (node (ref "LED62") (pin "A") (pinfunction "A_A") (pintype "passive"))
      (node (ref "LED63") (pin "C") (pinfunction "C_C") (pintype "passive"))
      (node (ref "TP12") (pin "TP") (pinfunction "TP_TP") (pintype "input"))
    )
    (net (code "11") (name "Net-(LED58-PadC)") (class "Default")
      (node (ref "LED58") (pin "C") (pinfunction "C_C") (pintype "passive"))
      (node (ref "LED59") (pin "A") (pinfunction "A_A") (pintype "passive"))
      (node (ref "LED60") (pin "C") (pinfunction "C_C") (pintype "passive"))
      (node (ref "LED61") (pin "A") (pinfunction "A_A") (pintype "passive"))
      (node (ref "TP14") (pin "TP") (pinfunction "TP_TP") (pintype "input"))
    )
    (net (code "12") (name "Net-(LED60-PadA)") (class "Default")
      (node (ref "LED60") (pin "A") (pinfunction "A_A") (pintype "passive"))
      (node (ref "LED61") (pin "C") (pinfunction "C_C") (pintype "passive"))
      (node (ref "LED64") (pin "A") (pinfunction "A_A") (pintype "passive"))
      (node (ref "LED65") (pin "C") (pinfunction "C_C") (pintype "passive"))
      (node (ref "TP11") (pin "TP") (pinfunction "TP_TP") (pintype "input"))
    )
    (net (code "13") (name "Net-(LED62-PadC)") (class "Default")
      (node (ref "LED62") (pin "C") (pinfunction "C_C") (pintype "passive"))
      (node (ref "LED63") (pin "A") (pinfunction "A_A") (pintype "passive"))
      (node (ref "LED64") (pin "C") (pinfunction "C_C") (pintype "passive"))
      (node (ref "LED65") (pin "A") (pinfunction "A_A") (pintype "passive"))
      (node (ref "TP13") (pin "TP") (pinfunction "TP_TP") (pintype "input"))
    )
    (net (code "14") (name "Net-(LED66-PadA)") (class "Default")
      (node (ref "LED66") (pin "A") (pinfunction "A_A") (pintype "passive"))
      (node (ref "LED67") (pin "C") (pinfunction "C_C") (pintype "passive"))
      (node (ref "LED70") (pin "A") (pinfunction "A_A") (pintype "passive"))
      (node (ref "LED71") (pin "C") (pinfunction "C_C") (pintype "passive"))
      (node (ref "LED74") (pin "A") (pinfunction "A_A") (pintype "passive"))
      (node (ref "LED75") (pin "C") (pinfunction "C_C") (pintype "passive"))
      (node (ref "LED78") (pin "A") (pinfunction "A_A") (pintype "passive"))
      (node (ref "LED79") (pin "C") (pinfunction "C_C") (pintype "passive"))
      (node (ref "TP15") (pin "TP") (pinfunction "TP_TP") (pintype "input"))
      (node (ref "TP8") (pin "TP") (pinfunction "TP_TP") (pintype "input"))
    )
    (net (code "15") (name "Net-(LED66-PadC)") (class "Default")
      (node (ref "LED66") (pin "C") (pinfunction "C_C") (pintype "passive"))
      (node (ref "LED67") (pin "A") (pinfunction "A_A") (pintype "passive"))
      (node (ref "LED68") (pin "C") (pinfunction "C_C") (pintype "passive"))
      (node (ref "LED69") (pin "A") (pinfunction "A_A") (pintype "passive"))
      (node (ref "LED74") (pin "C") (pinfunction "C_C") (pintype "passive"))
      (node (ref "LED75") (pin "A") (pinfunction "A_A") (pintype "passive"))
      (node (ref "LED76") (pin "C") (pinfunction "C_C") (pintype "passive"))
      (node (ref "LED77") (pin "A") (pinfunction "A_A") (pintype "passive"))
      (node (ref "TP10") (pin "TP") (pinfunction "TP_TP") (pintype "input"))
      (node (ref "TP17") (pin "TP") (pinfunction "TP_TP") (pintype "input"))
    )
    (net (code "16") (name "Net-(LED68-PadA)") (class "Default")
      (node (ref "LED68") (pin "A") (pinfunction "A_A") (pintype "passive"))
      (node (ref "LED69") (pin "C") (pinfunction "C_C") (pintype "passive"))
      (node (ref "LED72") (pin "A") (pinfunction "A_A") (pintype "passive"))
      (node (ref "LED73") (pin "C") (pinfunction "C_C") (pintype "passive"))
      (node (ref "LED76") (pin "A") (pinfunction "A_A") (pintype "passive"))
      (node (ref "LED77") (pin "C") (pinfunction "C_C") (pintype "passive"))
      (node (ref "LED80") (pin "A") (pinfunction "A_A") (pintype "passive"))
      (node (ref "LED81") (pin "C") (pinfunction "C_C") (pintype "passive"))
      (node (ref "TP16") (pin "TP") (pinfunction "TP_TP") (pintype "input"))
      (node (ref "TP7") (pin "TP") (pinfunction "TP_TP") (pintype "input"))
    )
    (net (code "17") (name "Net-(LED70-PadC)") (class "Default")
      (node (ref "LED70") (pin "C") (pinfunction "C_C") (pintype "passive"))
      (node (ref "LED71") (pin "A") (pinfunction "A_A") (pintype "passive"))
      (node (ref "LED72") (pin "C") (pinfunction "C_C") (pintype "passive"))
      (node (ref "LED73") (pin "A") (pinfunction "A_A") (pintype "passive"))
      (node (ref "LED78") (pin "C") (pinfunction "C_C") (pintype "passive"))
      (node (ref "LED79") (pin "A") (pinfunction "A_A") (pintype "passive"))
      (node (ref "LED80") (pin "C") (pinfunction "C_C") (pintype "passive"))
      (node (ref "LED81") (pin "A") (pinfunction "A_A") (pintype "passive"))
      (node (ref "TP18") (pin "TP") (pinfunction "TP_TP") (pintype "input"))
      (node (ref "TP9") (pin "TP") (pinfunction "TP_TP") (pintype "input"))
    )
    (net (code "18") (name "Net-(LED82-PadA)") (class "Default")
      (node (ref "LED82") (pin "A") (pinfunction "A_A") (pintype "passive"))
      (node (ref "LED83") (pin "C") (pinfunction "C_C") (pintype "passive"))
      (node (ref "LED86") (pin "A") (pinfunction "A_A") (pintype "passive"))
      (node (ref "LED87") (pin "C") (pinfunction "C_C") (pintype "passive"))
      (node (ref "TP20") (pin "TP") (pinfunction "TP_TP") (pintype "input"))
      (node (ref "TP25") (pin "TP") (pinfunction "TP_TP") (pintype "input"))
    )
    (net (code "19") (name "Net-(LED82-PadC)") (class "Default")
      (node (ref "LED82") (pin "C") (pinfunction "C_C") (pintype "passive"))
      (node (ref "LED83") (pin "A") (pinfunction "A_A") (pintype "passive"))
      (node (ref "LED84") (pin "C") (pinfunction "C_C") (pintype "passive"))
      (node (ref "LED85") (pin "A") (pinfunction "A_A") (pintype "passive"))
      (node (ref "TP22") (pin "TP") (pinfunction "TP_TP") (pintype "input"))
      (node (ref "TP23") (pin "TP") (pinfunction "TP_TP") (pintype "input"))
    )
    (net (code "20") (name "Net-(LED84-PadA)") (class "Default")
      (node (ref "LED84") (pin "A") (pinfunction "A_A") (pintype "passive"))
      (node (ref "LED85") (pin "C") (pinfunction "C_C") (pintype "passive"))
      (node (ref "LED88") (pin "A") (pinfunction "A_A") (pintype "passive"))
      (node (ref "LED89") (pin "C") (pinfunction "C_C") (pintype "passive"))
      (node (ref "TP19") (pin "TP") (pinfunction "TP_TP") (pintype "input"))
      (node (ref "TP26") (pin "TP") (pinfunction "TP_TP") (pintype "input"))
    )
    (net (code "21") (name "Net-(LED86-PadC)") (class "Default")
      (node (ref "LED86") (pin "C") (pinfunction "C_C") (pintype "passive"))
      (node (ref "LED87") (pin "A") (pinfunction "A_A") (pintype "passive"))
      (node (ref "LED88") (pin "C") (pinfunction "C_C") (pintype "passive"))
      (node (ref "LED89") (pin "A") (pinfunction "A_A") (pintype "passive"))
      (node (ref "TP21") (pin "TP") (pinfunction "TP_TP") (pintype "input"))
      (node (ref "TP24") (pin "TP") (pinfunction "TP_TP") (pintype "input"))
    )
    (net (code "22") (name "Net-(LED90-PadA)") (class "Default")
      (node (ref "LED90") (pin "A") (pinfunction "A_A") (pintype "passive"))
      (node (ref "LED91") (pin "C") (pinfunction "C_C") (pintype "passive"))
      (node (ref "TP27") (pin "TP") (pinfunction "TP_TP") (pintype "input"))
      (node (ref "TP28") (pin "TP") (pinfunction "TP_TP") (pintype "input"))
    )
    (net (code "23") (name "Net-(LED90-PadC)") (class "Default")
      (node (ref "LED90") (pin "C") (pinfunction "C_C") (pintype "passive"))
      (node (ref "R17") (pin "2") (pinfunction "2_2") (pintype "passive"))
    )
    (net (code "24") (name "Net-(LED91-PadA)") (class "Default")
      (node (ref "LED91") (pin "A") (pinfunction "A_A") (pintype "passive"))
      (node (ref "R12") (pin "2") (pinfunction "2_2") (pintype "passive"))
    )
    (net (code "25") (name "Net-(LED92-PadA)") (class "Default")
      (node (ref "LED92") (pin "A") (pinfunction "A_A") (pintype "passive"))
      (node (ref "LED93") (pin "C") (pinfunction "C_C") (pintype "passive"))
      (node (ref "TP31") (pin "TP") (pinfunction "TP_TP") (pintype "input"))
      (node (ref "TP32") (pin "TP") (pinfunction "TP_TP") (pintype "input"))
    )
    (net (code "26") (name "Net-(LED92-PadC)") (class "Default")
      (node (ref "LED92") (pin "C") (pinfunction "C_C") (pintype "passive"))
      (node (ref "R18") (pin "2") (pinfunction "2_2") (pintype "passive"))
    )
    (net (code "27") (name "Net-(LED93-PadA)") (class "Default")
      (node (ref "LED93") (pin "A") (pinfunction "A_A") (pintype "passive"))
      (node (ref "R13") (pin "2") (pinfunction "2_2") (pintype "passive"))
    )
    (net (code "28") (name "Net-(LED94-PadA)") (class "Default")
      (node (ref "LED94") (pin "A") (pinfunction "A_A") (pintype "passive"))
      (node (ref "LED95") (pin "C") (pinfunction "C_C") (pintype "passive"))
      (node (ref "TP35") (pin "TP") (pinfunction "TP_TP") (pintype "input"))
      (node (ref "TP36") (pin "TP") (pinfunction "TP_TP") (pintype "input"))
    )
    (net (code "29") (name "Net-(LED94-PadC)") (class "Default")
      (node (ref "LED94") (pin "C") (pinfunction "C_C") (pintype "passive"))
      (node (ref "R19") (pin "2") (pinfunction "2_2") (pintype "passive"))
    )
    (net (code "30") (name "Net-(LED95-PadA)") (class "Default")
      (node (ref "LED95") (pin "A") (pinfunction "A_A") (pintype "passive"))
      (node (ref "R14") (pin "2") (pinfunction "2_2") (pintype "passive"))
    )
    (net (code "31") (name "Net-(LED96-PadA)") (class "Default")
      (node (ref "LED96") (pin "A") (pinfunction "A_A") (pintype "passive"))
      (node (ref "LED97") (pin "C") (pinfunction "C_C") (pintype "passive"))
      (node (ref "TP39") (pin "TP") (pinfunction "TP_TP") (pintype "input"))
      (node (ref "TP40") (pin "TP") (pinfunction "TP_TP") (pintype "input"))
    )
    (net (code "32") (name "Net-(LED96-PadC)") (class "Default")
      (node (ref "LED96") (pin "C") (pinfunction "C_C") (pintype "passive"))
      (node (ref "R21") (pin "2") (pinfunction "2_2") (pintype "passive"))
    )
    (net (code "33") (name "Net-(LED97-PadA)") (class "Default")
      (node (ref "LED97") (pin "A") (pinfunction "A_A") (pintype "passive"))
      (node (ref "R15") (pin "2") (pinfunction "2_2") (pintype "passive"))
    )
    (net (code "34") (name "Net-(LED98-PadA)") (class "Default")
      (node (ref "LED98") (pin "A") (pinfunction "A_A") (pintype "passive"))
      (node (ref "LED99") (pin "C") (pinfunction "C_C") (pintype "passive"))
      (node (ref "TP43") (pin "TP") (pinfunction "TP_TP") (pintype "input"))
      (node (ref "TP44") (pin "TP") (pinfunction "TP_TP") (pintype "input"))
    )
    (net (code "35") (name "Net-(LED98-PadC)") (class "Default")
      (node (ref "LED98") (pin "C") (pinfunction "C_C") (pintype "passive"))
      (node (ref "R20") (pin "2") (pinfunction "2_2") (pintype "passive"))
    )
    (net (code "36") (name "Net-(LED99-PadA)") (class "Default")
      (node (ref "LED99") (pin "A") (pinfunction "A_A") (pintype "passive"))
      (node (ref "R16") (pin "2") (pinfunction "2_2") (pintype "passive"))
    )
    (net (code "37") (name "Net-(R12-Pad1)") (class "Default")
      (node (ref "R12") (pin "1") (pinfunction "1_1") (pintype "passive"))
      (node (ref "R17") (pin "1") (pinfunction "1_1") (pintype "passive"))
      (node (ref "TP29") (pin "TP") (pinfunction "TP_TP") (pintype "input"))
      (node (ref "TP30") (pin "TP") (pinfunction "TP_TP") (pintype "input"))
    )
    (net (code "38") (name "Net-(R13-Pad1)") (class "Default")
      (node (ref "R13") (pin "1") (pinfunction "1_1") (pintype "passive"))
      (node (ref "R18") (pin "1") (pinfunction "1_1") (pintype "passive"))
      (node (ref "TP33") (pin "TP") (pinfunction "TP_TP") (pintype "input"))
      (node (ref "TP34") (pin "TP") (pinfunction "TP_TP") (pintype "input"))
    )
    (net (code "39") (name "Net-(R14-Pad1)") (class "Default")
      (node (ref "R14") (pin "1") (pinfunction "1_1") (pintype "passive"))
      (node (ref "R19") (pin "1") (pinfunction "1_1") (pintype "passive"))
      (node (ref "TP37") (pin "TP") (pinfunction "TP_TP") (pintype "input"))
      (node (ref "TP38") (pin "TP") (pinfunction "TP_TP") (pintype "input"))
    )
    (net (code "40") (name "Net-(R15-Pad1)") (class "Default")
      (node (ref "R15") (pin "1") (pinfunction "1_1") (pintype "passive"))
      (node (ref "R21") (pin "1") (pinfunction "1_1") (pintype "passive"))
      (node (ref "TP41") (pin "TP") (pinfunction "TP_TP") (pintype "input"))
      (node (ref "TP42") (pin "TP") (pinfunction "TP_TP") (pintype "input"))
    )
    (net (code "41") (name "Net-(R16-Pad1)") (class "Default")
      (node (ref "R16") (pin "1") (pinfunction "1_1") (pintype "passive"))
      (node (ref "R20") (pin "1") (pinfunction "1_1") (pintype "passive"))
      (node (ref "TP45") (pin "TP") (pinfunction "TP_TP") (pintype "input"))
      (node (ref "TP46") (pin "TP") (pinfunction "TP_TP") (pintype "input"))
    )
    (net (code "42") (name "Net-(U$1-REXT)") (class "Default")
      (node (ref "R1") (pin "2") (pinfunction "2_2") (pintype "passive"))
      (node (ref "U$1") (pin "1") (pinfunction "REXT_1") (pintype "bidirectional"))
    )
    (net (code "43") (name "Net-(U$1-{slash}OUT0)") (class "Default")
      (node (ref "U$1") (pin "6") (pinfunction "/OUT0_6") (pintype "bidirectional"))
      (node (ref "U$6") (pin "B") (pinfunction "C_B") (pintype "bidirectional"))
    )
    (net (code "44") (name "Net-(U$1-{slash}OUT1)") (class "Default")
      (node (ref "U$1") (pin "7") (pinfunction "/OUT1_7") (pintype "bidirectional"))
      (node (ref "U$6") (pin "C") (pinfunction "B_C") (pintype "bidirectional"))
    )
    (net (code "45") (name "Net-(U$1-{slash}OUT2)") (class "Default")
      (node (ref "U$1") (pin "8") (pinfunction "/OUT2_8") (pintype "bidirectional"))
      (node (ref "U$6") (pin "V+") (pinfunction "A_V+") (pintype "bidirectional"))
    )
    (net (code "46") (name "Net-(U$1-{slash}OUT3)") (class "Default")
      (node (ref "LED10") (pin "C") (pinfunction "C_C") (pintype "passive"))
      (node (ref "U$1") (pin "9") (pinfunction "/OUT3_9") (pintype "bidirectional"))
    )
    (net (code "47") (name "Net-(U$1-{slash}OUT4)") (class "Default")
      (node (ref "U$1") (pin "11") (pinfunction "/OUT4_11") (pintype "bidirectional"))
      (node (ref "U$7") (pin "V+") (pinfunction "A_V+") (pintype "bidirectional"))
    )
    (net (code "48") (name "Net-(U$1-{slash}OUT5)") (class "Default")
      (node (ref "U$1") (pin "12") (pinfunction "/OUT5_12") (pintype "bidirectional"))
      (node (ref "U$8") (pin "B") (pinfunction "C_B") (pintype "bidirectional"))
    )
    (net (code "49") (name "Net-(U$1-{slash}OUT6)") (class "Default")
      (node (ref "U$1") (pin "13") (pinfunction "/OUT6_13") (pintype "bidirectional"))
      (node (ref "U$8") (pin "C") (pinfunction "B_C") (pintype "bidirectional"))
    )
    (net (code "50") (name "Net-(U$1-{slash}OUT7)") (class "Default")
      (node (ref "U$1") (pin "14") (pinfunction "/OUT7_14") (pintype "bidirectional"))
      (node (ref "U$8") (pin "V+") (pinfunction "A_V+") (pintype "bidirectional"))
    )
    (net (code "51") (name "Net-(U$1-{slash}OUT8)") (class "Default")
      (node (ref "U$1") (pin "15") (pinfunction "/OUT8_15") (pintype "bidirectional"))
      (node (ref "U$7") (pin "B") (pinfunction "C_B") (pintype "bidirectional"))
    )
    (net (code "52") (name "Net-(U$1-{slash}OUT9)") (class "Default")
      (node (ref "U$1") (pin "16") (pinfunction "/OUT9_16") (pintype "bidirectional"))
      (node (ref "U$7") (pin "C") (pinfunction "B_C") (pintype "bidirectional"))
    )
    (net (code "53") (name "Net-(U$1-{slash}OUT10)") (class "Default")
      (node (ref "U$1") (pin "17") (pinfunction "/OUT10_17") (pintype "bidirectional"))
      (node (ref "U$9") (pin "V+") (pinfunction "A_V+") (pintype "bidirectional"))
    )
    (net (code "54") (name "Net-(U$1-{slash}OUT11)") (class "Default")
      (node (ref "U$1") (pin "18") (pinfunction "/OUT11_18") (pintype "bidirectional"))
      (node (ref "U$9") (pin "C") (pinfunction "B_C") (pintype "bidirectional"))
    )
    (net (code "55") (name "Net-(U$1-{slash}OUT12)") (class "Default")
      (node (ref "U$1") (pin "20") (pinfunction "/OUT12_20") (pintype "bidirectional"))
      (node (ref "U$9") (pin "B") (pinfunction "C_B") (pintype "bidirectional"))
    )
    (net (code "56") (name "Net-(U$1-{slash}OUT13)") (class "Default")
      (node (ref "U$1") (pin "21") (pinfunction "/OUT13_21") (pintype "bidirectional"))
      (node (ref "U$10") (pin "V+") (pinfunction "A_V+") (pintype "bidirectional"))
    )
    (net (code "57") (name "Net-(U$1-{slash}OUT14)") (class "Default")
      (node (ref "U$1") (pin "22") (pinfunction "/OUT14_22") (pintype "bidirectional"))
      (node (ref "U$10") (pin "C") (pinfunction "B_C") (pintype "bidirectional"))
    )
    (net (code "58") (name "Net-(U$1-{slash}OUT15)") (class "Default")
      (node (ref "U$1") (pin "23") (pinfunction "/OUT15_23") (pintype "bidirectional"))
      (node (ref "U$10") (pin "B") (pinfunction "C_B") (pintype "bidirectional"))
    )
    (net (code "59") (name "Net-(U$1-{slash}RESET)") (class "Default")
      (node (ref "R2") (pin "2") (pinfunction "2_2") (pintype "passive"))
      (node (ref "U$1") (pin "25") (pinfunction "/RESET_25") (pintype "bidirectional"))
    )
    (net (code "60") (name "Net-(U$2-REXT)") (class "Default")
      (node (ref "R3") (pin "2") (pinfunction "2_2") (pintype "passive"))
      (node (ref "U$2") (pin "1") (pinfunction "REXT_1") (pintype "bidirectional"))
    )
    (net (code "61") (name "Net-(U$2-{slash}OUT0)") (class "Default")
      (node (ref "U$2") (pin "6") (pinfunction "/OUT0_6") (pintype "bidirectional"))
      (node (ref "U$3") (pin "B") (pinfunction "C_B") (pintype "bidirectional"))
    )
    (net (code "62") (name "Net-(U$2-{slash}OUT1)") (class "Default")
      (node (ref "U$2") (pin "7") (pinfunction "/OUT1_7") (pintype "bidirectional"))
      (node (ref "U$3") (pin "C") (pinfunction "B_C") (pintype "bidirectional"))
    )
    (net (code "63") (name "Net-(U$2-{slash}OUT2)") (class "Default")
      (node (ref "U$2") (pin "8") (pinfunction "/OUT2_8") (pintype "bidirectional"))
      (node (ref "U$3") (pin "V+") (pinfunction "A_V+") (pintype "bidirectional"))
    )
    (net (code "64") (name "Net-(U$2-{slash}OUT3)") (class "Default")
      (node (ref "LED11") (pin "C") (pinfunction "C_C") (pintype "passive"))
      (node (ref "U$2") (pin "9") (pinfunction "/OUT3_9") (pintype "bidirectional"))
    )
    (net (code "65") (name "Net-(U$2-{slash}OUT4)") (class "Default")
      (node (ref "U$2") (pin "11") (pinfunction "/OUT4_11") (pintype "bidirectional"))
      (node (ref "U$4") (pin "V+") (pinfunction "A_V+") (pintype "bidirectional"))
    )
    (net (code "66") (name "Net-(U$2-{slash}OUT8)") (class "Default")
      (node (ref "U$2") (pin "15") (pinfunction "/OUT8_15") (pintype "bidirectional"))
      (node (ref "U$4") (pin "B") (pinfunction "C_B") (pintype "bidirectional"))
    )
    (net (code "67") (name "Net-(U$2-{slash}OUT9)") (class "Default")
      (node (ref "U$2") (pin "16") (pinfunction "/OUT9_16") (pintype "bidirectional"))
      (node (ref "U$4") (pin "C") (pinfunction "B_C") (pintype "bidirectional"))
    )
    (net (code "68") (name "Net-(U$2-{slash}RESET)") (class "Default")
      (node (ref "R4") (pin "2") (pinfunction "2_2") (pintype "passive"))
      (node (ref "U$2") (pin "25") (pinfunction "/RESET_25") (pintype "bidirectional"))
    )
    (net (code "69") (name "Net-(U$11-A)") (class "Default")
      (node (ref "U$11") (pin "V+") (pinfunction "A_V+") (pintype "bidirectional"))
      (node (ref "U$2") (pin "14") (pinfunction "/OUT7_14") (pintype "bidirectional"))
    )
    (net (code "70") (name "Net-(U$11-B)") (class "Default")
      (node (ref "U$11") (pin "C") (pinfunction "B_C") (pintype "bidirectional"))
      (node (ref "U$2") (pin "13") (pinfunction "/OUT6_13") (pintype "bidirectional"))
    )
    (net (code "71") (name "Net-(U$11-C)") (class "Default")
      (node (ref "U$11") (pin "B") (pinfunction "C_B") (pintype "bidirectional"))
      (node (ref "U$2") (pin "12") (pinfunction "/OUT5_12") (pintype "bidirectional"))
    )
    (net (code "72") (name "Net-(U$12-A)") (class "Default")
      (node (ref "U$12") (pin "V+") (pinfunction "A_V+") (pintype "bidirectional"))
      (node (ref "U$2") (pin "17") (pinfunction "/OUT10_17") (pintype "bidirectional"))
    )
    (net (code "73") (name "Net-(U$12-B)") (class "Default")
      (node (ref "U$12") (pin "C") (pinfunction "B_C") (pintype "bidirectional"))
      (node (ref "U$2") (pin "18") (pinfunction "/OUT11_18") (pintype "bidirectional"))
    )
    (net (code "74") (name "Net-(U$12-C)") (class "Default")
      (node (ref "U$12") (pin "B") (pinfunction "C_B") (pintype "bidirectional"))
      (node (ref "U$2") (pin "20") (pinfunction "/OUT12_20") (pintype "bidirectional"))
    )
    (net (code "75") (name "Net-(U$13-A)") (class "Default")
      (node (ref "U$13") (pin "V+") (pinfunction "A_V+") (pintype "bidirectional"))
      (node (ref "U$2") (pin "21") (pinfunction "/OUT13_21") (pintype "bidirectional"))
    )
    (net (code "76") (name "Net-(U$13-B)") (class "Default")
      (node (ref "U$13") (pin "C") (pinfunction "B_C") (pintype "bidirectional"))
      (node (ref "U$2") (pin "22") (pinfunction "/OUT14_22") (pintype "bidirectional"))
    )
    (net (code "77") (name "Net-(U$13-C)") (class "Default")
      (node (ref "U$13") (pin "B") (pinfunction "C_B") (pintype "bidirectional"))
      (node (ref "U$2") (pin "23") (pinfunction "/OUT15_23") (pintype "bidirectional"))
    )
    (net (code "78") (name "Net-(U$14-REXT)") (class "Default")
      (node (ref "R5") (pin "2") (pinfunction "2_2") (pintype "passive"))
      (node (ref "U$14") (pin "1") (pinfunction "REXT_1") (pintype "bidirectional"))
    )
    (net (code "79") (name "Net-(U$14-{slash}OUT0)") (class "Default")
      (node (ref "U$14") (pin "6") (pinfunction "/OUT0_6") (pintype "bidirectional"))
      (node (ref "U$15") (pin "B") (pinfunction "C_B") (pintype "bidirectional"))
    )
    (net (code "80") (name "Net-(U$14-{slash}OUT1)") (class "Default")
      (node (ref "U$14") (pin "7") (pinfunction "/OUT1_7") (pintype "bidirectional"))
      (node (ref "U$15") (pin "C") (pinfunction "B_C") (pintype "bidirectional"))
    )
    (net (code "81") (name "Net-(U$14-{slash}OUT2)") (class "Default")
      (node (ref "U$14") (pin "8") (pinfunction "/OUT2_8") (pintype "bidirectional"))
      (node (ref "U$15") (pin "V+") (pinfunction "A_V+") (pintype "bidirectional"))
    )
    (net (code "82") (name "Net-(U$14-{slash}OUT3)") (class "Default")
      (node (ref "LED12") (pin "C") (pinfunction "C_C") (pintype "passive"))
      (node (ref "U$14") (pin "9") (pinfunction "/OUT3_9") (pintype "bidirectional"))
    )
    (net (code "83") (name "Net-(U$14-{slash}OUT4)") (class "Default")
      (node (ref "U$14") (pin "11") (pinfunction "/OUT4_11") (pintype "bidirectional"))
      (node (ref "U$16") (pin "V+") (pinfunction "A_V+") (pintype "bidirectional"))
    )
    (net (code "84") (name "Net-(U$14-{slash}OUT5)") (class "Default")
      (node (ref "U$14") (pin "12") (pinfunction "/OUT5_12") (pintype "bidirectional"))
      (node (ref "U$17") (pin "B") (pinfunction "C_B") (pintype "bidirectional"))
    )
    (net (code "85") (name "Net-(U$14-{slash}OUT6)") (class "Default")
      (node (ref "U$14") (pin "13") (pinfunction "/OUT6_13") (pintype "bidirectional"))
      (node (ref "U$17") (pin "C") (pinfunction "B_C") (pintype "bidirectional"))
    )
    (net (code "86") (name "Net-(U$14-{slash}OUT7)") (class "Default")
      (node (ref "U$14") (pin "14") (pinfunction "/OUT7_14") (pintype "bidirectional"))
      (node (ref "U$17") (pin "V+") (pinfunction "A_V+") (pintype "bidirectional"))
    )
    (net (code "87") (name "Net-(U$14-{slash}OUT8)") (class "Default")
      (node (ref "U$14") (pin "15") (pinfunction "/OUT8_15") (pintype "bidirectional"))
      (node (ref "U$16") (pin "B") (pinfunction "C_B") (pintype "bidirectional"))
    )
    (net (code "88") (name "Net-(U$14-{slash}OUT9)") (class "Default")
      (node (ref "U$14") (pin "16") (pinfunction "/OUT9_16") (pintype "bidirectional"))
      (node (ref "U$16") (pin "C") (pinfunction "B_C") (pintype "bidirectional"))
    )
    (net (code "89") (name "Net-(U$14-{slash}OUT10)") (class "Default")
      (node (ref "U$14") (pin "17") (pinfunction "/OUT10_17") (pintype "bidirectional"))
      (node (ref "U$18") (pin "V+") (pinfunction "A_V+") (pintype "bidirectional"))
    )
    (net (code "90") (name "Net-(U$14-{slash}OUT11)") (class "Default")
      (node (ref "U$14") (pin "18") (pinfunction "/OUT11_18") (pintype "bidirectional"))
      (node (ref "U$18") (pin "C") (pinfunction "B_C") (pintype "bidirectional"))
    )
    (net (code "91") (name "Net-(U$14-{slash}OUT12)") (class "Default")
      (node (ref "U$14") (pin "20") (pinfunction "/OUT12_20") (pintype "bidirectional"))
      (node (ref "U$18") (pin "B") (pinfunction "C_B") (pintype "bidirectional"))
    )
    (net (code "92") (name "Net-(U$14-{slash}OUT13)") (class "Default")
      (node (ref "U$14") (pin "21") (pinfunction "/OUT13_21") (pintype "bidirectional"))
      (node (ref "U$19") (pin "V+") (pinfunction "A_V+") (pintype "bidirectional"))
    )
    (net (code "93") (name "Net-(U$14-{slash}OUT14)") (class "Default")
      (node (ref "U$14") (pin "22") (pinfunction "/OUT14_22") (pintype "bidirectional"))
      (node (ref "U$19") (pin "C") (pinfunction "B_C") (pintype "bidirectional"))
    )
    (net (code "94") (name "Net-(U$14-{slash}OUT15)") (class "Default")
      (node (ref "U$14") (pin "23") (pinfunction "/OUT15_23") (pintype "bidirectional"))
      (node (ref "U$19") (pin "B") (pinfunction "C_B") (pintype "bidirectional"))
    )
    (net (code "95") (name "Net-(U$14-{slash}RESET)") (class "Default")
      (node (ref "R6") (pin "2") (pinfunction "2_2") (pintype "passive"))
      (node (ref "U$14") (pin "25") (pinfunction "/RESET_25") (pintype "bidirectional"))
    )
    (net (code "96") (name "Net-(U$20-REXT)") (class "Default")
      (node (ref "R7") (pin "2") (pinfunction "2_2") (pintype "passive"))
      (node (ref "U$20") (pin "1") (pinfunction "REXT_1") (pintype "bidirectional"))
    )
    (net (code "97") (name "Net-(U$20-{slash}OUT0)") (class "Default")
      (node (ref "U$20") (pin "6") (pinfunction "/OUT0_6") (pintype "bidirectional"))
      (node (ref "U$21") (pin "B") (pinfunction "C_B") (pintype "bidirectional"))
    )
    (net (code "98") (name "Net-(U$20-{slash}OUT1)") (class "Default")
      (node (ref "U$20") (pin "7") (pinfunction "/OUT1_7") (pintype "bidirectional"))
      (node (ref "U$21") (pin "C") (pinfunction "B_C") (pintype "bidirectional"))
    )
    (net (code "99") (name "Net-(U$20-{slash}OUT2)") (class "Default")
      (node (ref "U$20") (pin "8") (pinfunction "/OUT2_8") (pintype "bidirectional"))
      (node (ref "U$21") (pin "V+") (pinfunction "A_V+") (pintype "bidirectional"))
    )
    (net (code "100") (name "Net-(U$20-{slash}OUT3)") (class "Default")
      (node (ref "LED13") (pin "C") (pinfunction "C_C") (pintype "passive"))
      (node (ref "U$20") (pin "9") (pinfunction "/OUT3_9") (pintype "bidirectional"))
    )
    (net (code "101") (name "Net-(U$20-{slash}OUT4)") (class "Default")
      (node (ref "U$20") (pin "11") (pinfunction "/OUT4_11") (pintype "bidirectional"))
      (node (ref "U$22") (pin "V+") (pinfunction "A_V+") (pintype "bidirectional"))
    )
    (net (code "102") (name "Net-(U$20-{slash}OUT5)") (class "Default")
      (node (ref "U$20") (pin "12") (pinfunction "/OUT5_12") (pintype "bidirectional"))
      (node (ref "U$23") (pin "B") (pinfunction "C_B") (pintype "bidirectional"))
    )
    (net (code "103") (name "Net-(U$20-{slash}OUT6)") (class "Default")
      (node (ref "U$20") (pin "13") (pinfunction "/OUT6_13") (pintype "bidirectional"))
      (node (ref "U$23") (pin "C") (pinfunction "B_C") (pintype "bidirectional"))
    )
    (net (code "104") (name "Net-(U$20-{slash}OUT7)") (class "Default")
      (node (ref "U$20") (pin "14") (pinfunction "/OUT7_14") (pintype "bidirectional"))
      (node (ref "U$23") (pin "V+") (pinfunction "A_V+") (pintype "bidirectional"))
    )
    (net (code "105") (name "Net-(U$20-{slash}OUT8)") (class "Default")
      (node (ref "U$20") (pin "15") (pinfunction "/OUT8_15") (pintype "bidirectional"))
      (node (ref "U$22") (pin "B") (pinfunction "C_B") (pintype "bidirectional"))
    )
    (net (code "106") (name "Net-(U$20-{slash}OUT9)") (class "Default")
      (node (ref "U$20") (pin "16") (pinfunction "/OUT9_16") (pintype "bidirectional"))
      (node (ref "U$22") (pin "C") (pinfunction "B_C") (pintype "bidirectional"))
    )
    (net (code "107") (name "Net-(U$20-{slash}OUT10)") (class "Default")
      (node (ref "U$20") (pin "17") (pinfunction "/OUT10_17") (pintype "bidirectional"))
      (node (ref "U$24") (pin "V+") (pinfunction "A_V+") (pintype "bidirectional"))
    )
    (net (code "108") (name "Net-(U$20-{slash}OUT11)") (class "Default")
      (node (ref "U$20") (pin "18") (pinfunction "/OUT11_18") (pintype "bidirectional"))
      (node (ref "U$24") (pin "C") (pinfunction "B_C") (pintype "bidirectional"))
    )
    (net (code "109") (name "Net-(U$20-{slash}OUT12)") (class "Default")
      (node (ref "U$20") (pin "20") (pinfunction "/OUT12_20") (pintype "bidirectional"))
      (node (ref "U$24") (pin "B") (pinfunction "C_B") (pintype "bidirectional"))
    )
    (net (code "110") (name "Net-(U$20-{slash}OUT13)") (class "Default")
      (node (ref "U$20") (pin "21") (pinfunction "/OUT13_21") (pintype "bidirectional"))
      (node (ref "U$25") (pin "V+") (pinfunction "A_V+") (pintype "bidirectional"))
    )
    (net (code "111") (name "Net-(U$20-{slash}OUT14)") (class "Default")
      (node (ref "U$20") (pin "22") (pinfunction "/OUT14_22") (pintype "bidirectional"))
      (node (ref "U$25") (pin "C") (pinfunction "B_C") (pintype "bidirectional"))
    )
    (net (code "112") (name "Net-(U$20-{slash}OUT15)") (class "Default")
      (node (ref "U$20") (pin "23") (pinfunction "/OUT15_23") (pintype "bidirectional"))
      (node (ref "U$25") (pin "B") (pinfunction "C_B") (pintype "bidirectional"))
    )
    (net (code "113") (name "Net-(U$20-{slash}RESET)") (class "Default")
      (node (ref "R8") (pin "2") (pinfunction "2_2") (pintype "passive"))
      (node (ref "U$20") (pin "25") (pinfunction "/RESET_25") (pintype "bidirectional"))
    )
    (net (code "114") (name "Net-(U$26-A)") (class "Default")
      (node (ref "LED1") (pin "C") (pinfunction "C_C") (pintype "passive"))
      (node (ref "LED4") (pin "C") (pinfunction "C_C") (pintype "passive"))
      (node (ref "LED7") (pin "C") (pinfunction "C_C") (pintype "passive"))
      (node (ref "U$26") (pin "C") (pinfunction "A_C") (pintype "bidirectional"))
      (node (ref "U$5") (pin "V+") (pinfunction "A_V+") (pintype "bidirectional"))
    )
    (net (code "115") (name "Net-(U$26-B)") (class "Default")
      (node (ref "LED2") (pin "C") (pinfunction "C_C") (pintype "passive"))
      (node (ref "LED5") (pin "C") (pinfunction "C_C") (pintype "passive"))
      (node (ref "LED8") (pin "C") (pinfunction "C_C") (pintype "passive"))
      (node (ref "U$26") (pin "V+") (pinfunction "B_V+") (pintype "bidirectional"))
      (node (ref "U$5") (pin "C") (pinfunction "B_C") (pintype "bidirectional"))
    )
    (net (code "116") (name "Net-(U$26-C)") (class "Default")
      (node (ref "LED3") (pin "C") (pinfunction "C_C") (pintype "passive"))
      (node (ref "LED6") (pin "C") (pinfunction "C_C") (pintype "passive"))
      (node (ref "LED9") (pin "C") (pinfunction "C_C") (pintype "passive"))
      (node (ref "U$26") (pin "A") (pinfunction "C_A") (pintype "bidirectional"))
      (node (ref "U$5") (pin "B") (pinfunction "C_B") (pintype "bidirectional"))
    )
    (net (code "117") (name "Net-(U$26-V+)") (class "Default")
      (node (ref "LED1") (pin "A") (pinfunction "A_A") (pintype "passive"))
      (node (ref "LED2") (pin "A") (pinfunction "A_A") (pintype "passive"))
      (node (ref "LED3") (pin "A") (pinfunction "A_A") (pintype "passive"))
      (node (ref "LED4") (pin "A") (pinfunction "A_A") (pintype "passive"))
      (node (ref "LED5") (pin "A") (pinfunction "A_A") (pintype "passive"))
      (node (ref "LED6") (pin "A") (pinfunction "A_A") (pintype "passive"))
      (node (ref "LED7") (pin "A") (pinfunction "A_A") (pintype "passive"))
      (node (ref "LED8") (pin "A") (pinfunction "A_A") (pintype "passive"))
      (node (ref "LED9") (pin "A") (pinfunction "A_A") (pintype "passive"))
      (node (ref "U$26") (pin "B") (pinfunction "V+_B") (pintype "bidirectional"))
      (node (ref "U$5") (pin "A") (pinfunction "V+_A") (pintype "bidirectional"))
    )
    (net (code "118") (name "Net-(U$27-A)") (class "Default")
      (node (ref "LED14") (pin "C") (pinfunction "C_C") (pintype "passive"))
      (node (ref "LED17") (pin "C") (pinfunction "C_C") (pintype "passive"))
      (node (ref "LED20") (pin "C") (pinfunction "C_C") (pintype "passive"))
      (node (ref "U$27") (pin "C") (pinfunction "A_C") (pintype "bidirectional"))
      (node (ref "U$28") (pin "V+") (pinfunction "A_V+") (pintype "bidirectional"))
    )
    (net (code "119") (name "Net-(U$27-B)") (class "Default")
      (node (ref "LED15") (pin "C") (pinfunction "C_C") (pintype "passive"))
      (node (ref "LED18") (pin "C") (pinfunction "C_C") (pintype "passive"))
      (node (ref "LED21") (pin "C") (pinfunction "C_C") (pintype "passive"))
      (node (ref "U$27") (pin "V+") (pinfunction "B_V+") (pintype "bidirectional"))
      (node (ref "U$28") (pin "C") (pinfunction "B_C") (pintype "bidirectional"))
    )
    (net (code "120") (name "Net-(U$27-C)") (class "Default")
      (node (ref "LED16") (pin "C") (pinfunction "C_C") (pintype "passive"))
      (node (ref "LED19") (pin "C") (pinfunction "C_C") (pintype "passive"))
      (node (ref "LED22") (pin "C") (pinfunction "C_C") (pintype "passive"))
      (node (ref "U$27") (pin "A") (pinfunction "C_A") (pintype "bidirectional"))
      (node (ref "U$28") (pin "B") (pinfunction "C_B") (pintype "bidirectional"))
    )
    (net (code "121") (name "Net-(U$27-V+)") (class "Default")
      (node (ref "LED14") (pin "A") (pinfunction "A_A") (pintype "passive"))
      (node (ref "LED15") (pin "A") (pinfunction "A_A") (pintype "passive"))
      (node (ref "LED16") (pin "A") (pinfunction "A_A") (pintype "passive"))
      (node (ref "LED17") (pin "A") (pinfunction "A_A") (pintype "passive"))
      (node (ref "LED18") (pin "A") (pinfunction "A_A") (pintype "passive"))
      (node (ref "LED19") (pin "A") (pinfunction "A_A") (pintype "passive"))
      (node (ref "LED20") (pin "A") (pinfunction "A_A") (pintype "passive"))
      (node (ref "LED21") (pin "A") (pinfunction "A_A") (pintype "passive"))
      (node (ref "LED22") (pin "A") (pinfunction "A_A") (pintype "passive"))
      (node (ref "U$27") (pin "B") (pinfunction "V+_B") (pintype "bidirectional"))
      (node (ref "U$28") (pin "A") (pinfunction "V+_A") (pintype "bidirectional"))
    )
    (net (code "122") (name "Net-(U$29-A)") (class "Default")
      (node (ref "LED23") (pin "C") (pinfunction "C_C") (pintype "passive"))
      (node (ref "LED26") (pin "C") (pinfunction "C_C") (pintype "passive"))
      (node (ref "LED29") (pin "C") (pinfunction "C_C") (pintype "passive"))
      (node (ref "U$29") (pin "C") (pinfunction "A_C") (pintype "bidirectional"))
      (node (ref "U$30") (pin "V+") (pinfunction "A_V+") (pintype "bidirectional"))
    )
    (net (code "123") (name "Net-(U$29-B)") (class "Default")
      (node (ref "LED24") (pin "C") (pinfunction "C_C") (pintype "passive"))
      (node (ref "LED27") (pin "C") (pinfunction "C_C") (pintype "passive"))
      (node (ref "LED30") (pin "C") (pinfunction "C_C") (pintype "passive"))
      (node (ref "U$29") (pin "V+") (pinfunction "B_V+") (pintype "bidirectional"))
      (node (ref "U$30") (pin "C") (pinfunction "B_C") (pintype "bidirectional"))
    )
    (net (code "124") (name "Net-(U$29-C)") (class "Default")
      (node (ref "LED25") (pin "C") (pinfunction "C_C") (pintype "passive"))
      (node (ref "LED28") (pin "C") (pinfunction "C_C") (pintype "passive"))
      (node (ref "LED31") (pin "C") (pinfunction "C_C") (pintype "passive"))
      (node (ref "U$29") (pin "A") (pinfunction "C_A") (pintype "bidirectional"))
      (node (ref "U$30") (pin "B") (pinfunction "C_B") (pintype "bidirectional"))
    )
    (net (code "125") (name "Net-(U$29-V+)") (class "Default")
      (node (ref "LED23") (pin "A") (pinfunction "A_A") (pintype "passive"))
      (node (ref "LED24") (pin "A") (pinfunction "A_A") (pintype "passive"))
      (node (ref "LED25") (pin "A") (pinfunction "A_A") (pintype "passive"))
      (node (ref "LED26") (pin "A") (pinfunction "A_A") (pintype "passive"))
      (node (ref "LED27") (pin "A") (pinfunction "A_A") (pintype "passive"))
      (node (ref "LED28") (pin "A") (pinfunction "A_A") (pintype "passive"))
      (node (ref "LED29") (pin "A") (pinfunction "A_A") (pintype "passive"))
      (node (ref "LED30") (pin "A") (pinfunction "A_A") (pintype "passive"))
      (node (ref "LED31") (pin "A") (pinfunction "A_A") (pintype "passive"))
      (node (ref "U$29") (pin "B") (pinfunction "V+_B") (pintype "bidirectional"))
      (node (ref "U$30") (pin "A") (pinfunction "V+_A") (pintype "bidirectional"))
    )
    (net (code "126") (name "Net-(U$31-A)") (class "Default")
      (node (ref "LED32") (pin "C") (pinfunction "C_C") (pintype "passive"))
      (node (ref "LED35") (pin "C") (pinfunction "C_C") (pintype "passive"))
      (node (ref "LED38") (pin "C") (pinfunction "C_C") (pintype "passive"))
      (node (ref "U$31") (pin "C") (pinfunction "A_C") (pintype "bidirectional"))
      (node (ref "U$32") (pin "V+") (pinfunction "A_V+") (pintype "bidirectional"))
    )
    (net (code "127") (name "Net-(U$31-B)") (class "Default")
      (node (ref "LED33") (pin "C") (pinfunction "C_C") (pintype "passive"))
      (node (ref "LED36") (pin "C") (pinfunction "C_C") (pintype "passive"))
      (node (ref "LED39") (pin "C") (pinfunction "C_C") (pintype "passive"))
      (node (ref "U$31") (pin "V+") (pinfunction "B_V+") (pintype "bidirectional"))
      (node (ref "U$32") (pin "C") (pinfunction "B_C") (pintype "bidirectional"))
    )
    (net (code "128") (name "Net-(U$31-C)") (class "Default")
      (node (ref "LED34") (pin "C") (pinfunction "C_C") (pintype "passive"))
      (node (ref "LED37") (pin "C") (pinfunction "C_C") (pintype "passive"))
      (node (ref "LED40") (pin "C") (pinfunction "C_C") (pintype "passive"))
      (node (ref "U$31") (pin "A") (pinfunction "C_A") (pintype "bidirectional"))
      (node (ref "U$32") (pin "B") (pinfunction "C_B") (pintype "bidirectional"))
    )
    (net (code "129") (name "Net-(U$31-V+)") (class "Default")
      (node (ref "LED32") (pin "A") (pinfunction "A_A") (pintype "passive"))
      (node (ref "LED33") (pin "A") (pinfunction "A_A") (pintype "passive"))
      (node (ref "LED34") (pin "A") (pinfunction "A_A") (pintype "passive"))
      (node (ref "LED35") (pin "A") (pinfunction "A_A") (pintype "passive"))
      (node (ref "LED36") (pin "A") (pinfunction "A_A") (pintype "passive"))
      (node (ref "LED37") (pin "A") (pinfunction "A_A") (pintype "passive"))
      (node (ref "LED38") (pin "A") (pinfunction "A_A") (pintype "passive"))
      (node (ref "LED39") (pin "A") (pinfunction "A_A") (pintype "passive"))
      (node (ref "LED40") (pin "A") (pinfunction "A_A") (pintype "passive"))
      (node (ref "U$31") (pin "B") (pinfunction "V+_B") (pintype "bidirectional"))
      (node (ref "U$32") (pin "A") (pinfunction "V+_A") (pintype "bidirectional"))
    )
    (net (code "130") (name "Net-(U$33-A)") (class "Default")
      (node (ref "LED41") (pin "C") (pinfunction "C_C") (pintype "passive"))
      (node (ref "LED44") (pin "C") (pinfunction "C_C") (pintype "passive"))
      (node (ref "LED47") (pin "C") (pinfunction "C_C") (pintype "passive"))
      (node (ref "U$33") (pin "C") (pinfunction "A_C") (pintype "bidirectional"))
      (node (ref "U$34") (pin "V+") (pinfunction "A_V+") (pintype "bidirectional"))
    )
    (net (code "131") (name "Net-(U$33-B)") (class "Default")
      (node (ref "LED42") (pin "C") (pinfunction "C_C") (pintype "passive"))
      (node (ref "LED45") (pin "C") (pinfunction "C_C") (pintype "passive"))
      (node (ref "LED48") (pin "C") (pinfunction "C_C") (pintype "passive"))
      (node (ref "U$33") (pin "V+") (pinfunction "B_V+") (pintype "bidirectional"))
      (node (ref "U$34") (pin "C") (pinfunction "B_C") (pintype "bidirectional"))
    )
    (net (code "132") (name "Net-(U$33-C)") (class "Default")
      (node (ref "LED43") (pin "C") (pinfunction "C_C") (pintype "passive"))
      (node (ref "LED46") (pin "C") (pinfunction "C_C") (pintype "passive"))
      (node (ref "LED49") (pin "C") (pinfunction "C_C") (pintype "passive"))
      (node (ref "U$33") (pin "A") (pinfunction "C_A") (pintype "bidirectional"))
      (node (ref "U$34") (pin "B") (pinfunction "C_B") (pintype "bidirectional"))
    )
    (net (code "133") (name "Net-(U$33-V+)") (class "Default")
      (node (ref "LED41") (pin "A") (pinfunction "A_A") (pintype "passive"))
      (node (ref "LED42") (pin "A") (pinfunction "A_A") (pintype "passive"))
      (node (ref "LED43") (pin "A") (pinfunction "A_A") (pintype "passive"))
      (node (ref "LED44") (pin "A") (pinfunction "A_A") (pintype "passive"))
      (node (ref "LED45") (pin "A") (pinfunction "A_A") (pintype "passive"))
      (node (ref "LED46") (pin "A") (pinfunction "A_A") (pintype "passive"))
      (node (ref "LED47") (pin "A") (pinfunction "A_A") (pintype "passive"))
      (node (ref "LED48") (pin "A") (pinfunction "A_A") (pintype "passive"))
      (node (ref "LED49") (pin "A") (pinfunction "A_A") (pintype "passive"))
      (node (ref "U$33") (pin "B") (pinfunction "V+_B") (pintype "bidirectional"))
      (node (ref "U$34") (pin "A") (pinfunction "V+_A") (pintype "bidirectional"))
    )
    (net (code "134") (name "Net-(U1-PB1)") (class "Default")
      (node (ref "PB1") (pin "TP") (pinfunction "TP_TP") (pintype "input"))
      (node (ref "U1") (pin "6") (pinfunction "PB1_6") (pintype "bidirectional"))
    )
    (net (code "135") (name "Net-(U1-PB3)") (class "Default")
      (node (ref "PB3") (pin "TP") (pinfunction "TP_TP") (pintype "input"))
      (node (ref "U1") (pin "2") (pinfunction "PB3_2") (pintype "bidirectional"))
    )
    (net (code "136") (name "Net-(U1-PB4)") (class "Default")
      (node (ref "PB4") (pin "TP") (pinfunction "TP_TP") (pintype "input"))
      (node (ref "U1") (pin "3") (pinfunction "PB4_3") (pintype "bidirectional"))
    )
    (net (code "137") (name "Net-(U1-PB5)") (class "Default")
      (node (ref "RESET") (pin "TP") (pinfunction "TP_TP") (pintype "input"))
      (node (ref "U1") (pin "1") (pinfunction "PB5_1") (pintype "bidirectional"))
    )
  )
)
